# INC-IO1212001.net
KiCad netlist of a schematic drawn in Altium Designer
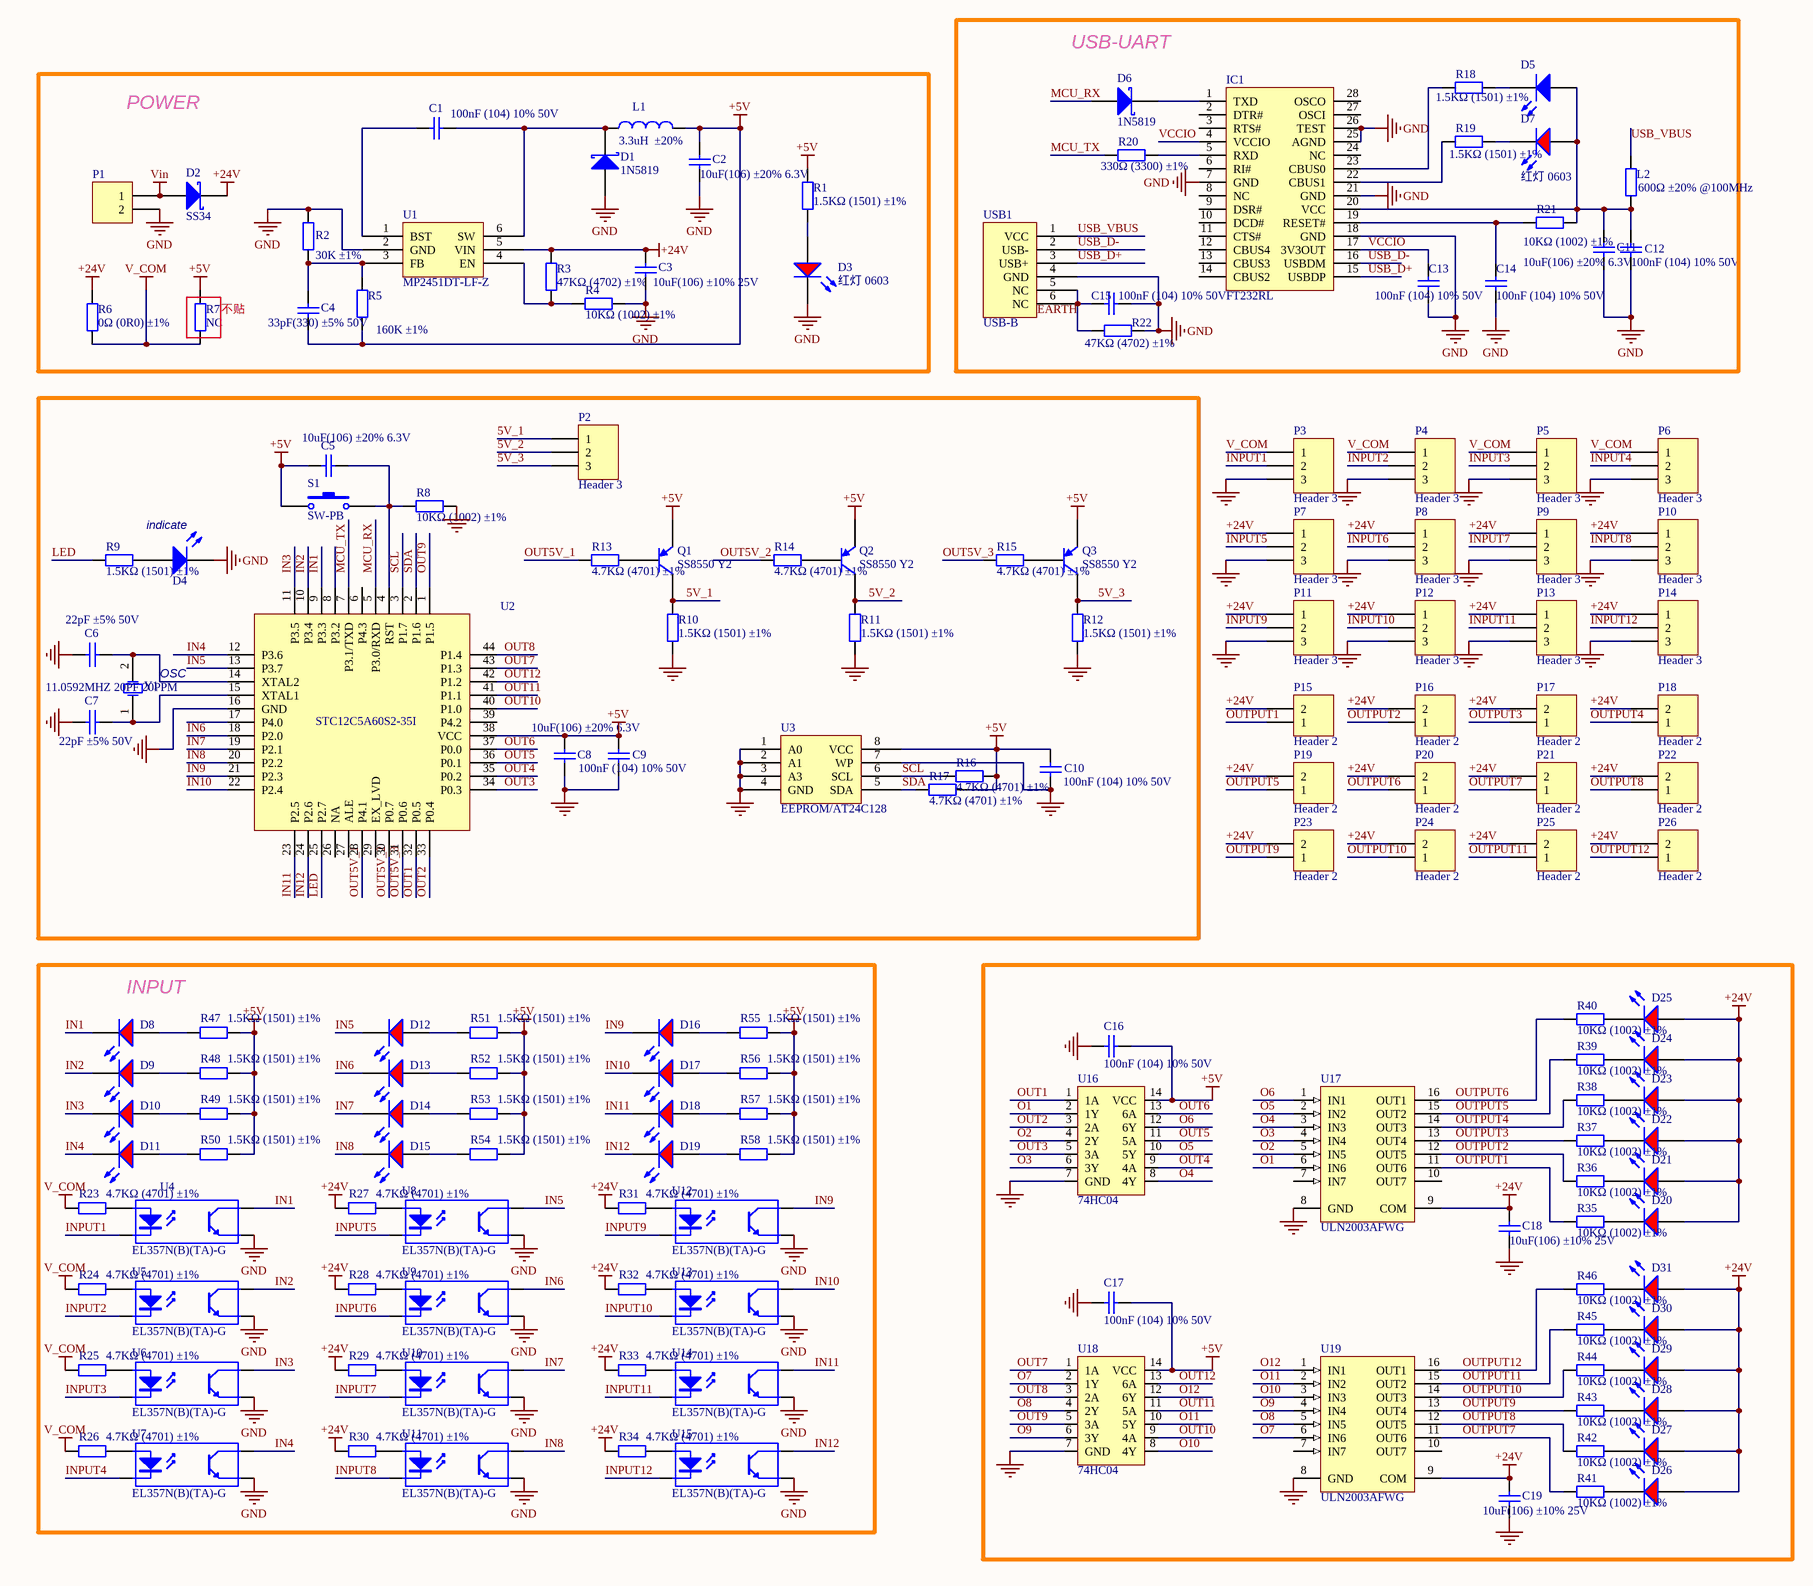
[diagram p0: INC-IO1212001.SchDoc]

(export (version "E")
  (design (tool "Eeschema 10.0.6"))
  (components
    (comp (ref "C1")
      (value "100nF (104) 10% 50V")
      (footprint "0603_C")
      (description "贴片电容")
      (libsource (lib "Miscellaneous Devices LC") (part "0603 10nF (103) 10% 50V"))
    )
    (comp (ref "C2")
      (value "10uF(106) ±20% 6.3V")
      (footprint "0603_C")
      (description "Capacitor")
      (fields (field (name "PUBLISHER") "Altium Limited"))
      (libsource (lib "Miscellaneous Devices") (part "Cap"))
    )
    (comp (ref "C3")
      (value "10uF(106) ±10% 25V")
      (footprint "1206_C")
      (description "Capacitor")
      (fields (field (name "PUBLISHER") "Altium Limited"))
      (libsource (lib "Miscellaneous Devices") (part "Cap"))
    )
    (comp (ref "C4")
      (value "33pF(330) ±5% 50V")
      (footprint "0603_C")
      (description "贴片电容")
      (libsource (lib "Miscellaneous Devices LC") (part "0603 10nF (103) 10% 50V"))
    )
    (comp (ref "C5")
      (value "10uF(106) ±20% 6.3V")
      (footprint "0603_C")
      (description "贴片电容")
      (libsource (lib "Miscellaneous Devices LC") (part "0603 10uF (106) 10% 10V"))
    )
    (comp (ref "C6")
      (value "22pF ±5% 50V")
      (footprint "0603_C")
      (description "Capacitor")
      (libsource (lib "*") (part "CAP"))
    )
    (comp (ref "C7")
      (value "22pF ±5% 50V")
      (footprint "0603_C")
      (description "Capacitor")
      (libsource (lib "*") (part "CAP"))
    )
    (comp (ref "C8")
      (value "10uF(106) ±20% 6.3V")
      (footprint "0603_C")
      (description "Capacitor")
      (fields (field (name "PUBLISHER") "Altium Limited"))
      (libsource (lib "Miscellaneous Devices") (part "Cap"))
    )
    (comp (ref "C9")
      (value "100nF (104) 10% 50V")
      (footprint "0603_C")
      (description "Capacitor")
      (fields (field (name "PUBLISHER") "Altium Limited"))
      (libsource (lib "Miscellaneous Devices") (part "Cap"))
    )
    (comp (ref "C10")
      (value "100nF (104) 10% 50V")
      (footprint "0603_C")
      (description "Capacitor")
      (fields (field (name "PUBLISHER") "Altium Limited"))
      (libsource (lib "Miscellaneous Devices") (part "Cap"))
    )
    (comp (ref "C11")
      (value "10uF(106) ±20% 6.3V")
      (footprint "0603_C")
      (description "Capacitor")
      (fields (field (name "PUBLISHER") "Altium Limited"))
      (libsource (lib "Miscellaneous Devices") (part "Cap"))
    )
    (comp (ref "C12")
      (value "100nF (104) 10% 50V")
      (footprint "0603_C")
      (description "Capacitor")
      (fields (field (name "PUBLISHER") "Altium Limited"))
      (libsource (lib "Miscellaneous Devices") (part "Cap"))
    )
    (comp (ref "C13")
      (value "100nF (104) 10% 50V")
      (footprint "0603_C")
      (description "Capacitor")
      (fields (field (name "PUBLISHER") "Altium Limited"))
      (libsource (lib "Miscellaneous Devices") (part "Cap"))
    )
    (comp (ref "C14")
      (value "100nF (104) 10% 50V")
      (footprint "0603_C")
      (description "Capacitor")
      (fields (field (name "PUBLISHER") "Altium Limited"))
      (libsource (lib "Miscellaneous Devices") (part "Cap"))
    )
    (comp (ref "C15")
      (value "100nF (104) 10% 50V")
      (footprint "0603_C")
      (description "Capacitor")
      (fields (field (name "PUBLISHER") "Altium Limited"))
      (libsource (lib "Miscellaneous Devices") (part "Cap"))
    )
    (comp (ref "C16")
      (value "100nF (104) 10% 50V")
      (footprint "0603_C")
      (description "Capacitor")
      (fields (field (name "PUBLISHER") "Altium Limited"))
      (libsource (lib "Miscellaneous Devices") (part "Cap"))
    )
    (comp (ref "C17")
      (value "100nF (104) 10% 50V")
      (footprint "0603_C")
      (description "Capacitor")
      (fields (field (name "PUBLISHER") "Altium Limited"))
      (libsource (lib "Miscellaneous Devices") (part "Cap"))
    )
    (comp (ref "C18")
      (value "10uF(106) ±10% 25V")
      (footprint "1206_C")
      (description "Capacitor")
      (fields (field (name "PUBLISHER") "Altium Limited"))
      (libsource (lib "Miscellaneous Devices") (part "Cap"))
    )
    (comp (ref "C19")
      (value "10uF(106) ±10% 25V")
      (footprint "1206_C")
      (description "Capacitor")
      (fields (field (name "PUBLISHER") "Altium Limited"))
      (libsource (lib "Miscellaneous Devices") (part "Cap"))
    )
    (comp (ref "D1")
      (value "1N5819")
      (footprint "SOD-123")
      (description "Schottky Diode")
      (fields (field (name "PUBLISHER") "Altium Limited"))
      (libsource (lib "Miscellaneous Devices") (part "D Schottky"))
    )
    (comp (ref "D2")
      (value "SS34")
      (footprint "SMA(DO-214AC)_S1")
      (description "Schottky Diode")
      (fields (field (name "PUBLISHER") "Altium Limited"))
      (libsource (lib "Miscellaneous Devices") (part "D Schottky"))
    )
    (comp (ref "D3")
      (value "红灯 0603")
      (footprint "0603_LED_S1")
      (description "发光二极管")
      (libsource (lib "Miscellaneous Devices LC") (part "0603 红灯"))
    )
    (comp (ref "D4")
      (value "蓝灯 0603")
      (footprint "0603_LED_S1")
      (description "发光二极管")
      (libsource (lib "Miscellaneous Devices LC") (part "0603 蓝灯"))
    )
    (comp (ref "D5")
      (value "蓝灯 0603")
      (footprint "0603_LED_S1")
      (description "发光二极管")
      (libsource (lib "Miscellaneous Devices LC") (part "0603 蓝灯"))
    )
    (comp (ref "D6")
      (value "1N5819")
      (footprint "SOD-123")
      (description "Schottky Diode")
      (fields (field (name "PUBLISHER") "Altium Limited"))
      (libsource (lib "Miscellaneous Devices") (part "D Schottky"))
    )
    (comp (ref "D7")
      (value "红灯 0603")
      (footprint "0603_LED_S1")
      (description "发光二极管")
      (libsource (lib "Miscellaneous Devices LC") (part "0603 红灯"))
    )
    (comp (ref "D8")
      (value "红灯 0603")
      (footprint "0603_LED_S1")
      (description "发光二极管")
      (libsource (lib "Miscellaneous Devices LC") (part "0603 红灯"))
    )
    (comp (ref "D9")
      (value "红灯 0603")
      (footprint "0603_LED_S1")
      (description "发光二极管")
      (libsource (lib "Miscellaneous Devices LC") (part "0603 红灯"))
    )
    (comp (ref "D10")
      (value "红灯 0603")
      (footprint "0603_LED_S1")
      (description "发光二极管")
      (libsource (lib "Miscellaneous Devices LC") (part "0603 红灯"))
    )
    (comp (ref "D11")
      (value "红灯 0603")
      (footprint "0603_LED_S1")
      (description "发光二极管")
      (libsource (lib "Miscellaneous Devices LC") (part "0603 红灯"))
    )
    (comp (ref "D12")
      (value "红灯 0603")
      (footprint "0603_LED_S1")
      (description "发光二极管")
      (libsource (lib "Miscellaneous Devices LC") (part "0603 红灯"))
    )
    (comp (ref "D13")
      (value "红灯 0603")
      (footprint "0603_LED_S1")
      (description "发光二极管")
      (libsource (lib "Miscellaneous Devices LC") (part "0603 红灯"))
    )
    (comp (ref "D14")
      (value "红灯 0603")
      (footprint "0603_LED_S1")
      (description "发光二极管")
      (libsource (lib "Miscellaneous Devices LC") (part "0603 红灯"))
    )
    (comp (ref "D15")
      (value "红灯 0603")
      (footprint "0603_LED_S1")
      (description "发光二极管")
      (libsource (lib "Miscellaneous Devices LC") (part "0603 红灯"))
    )
    (comp (ref "D16")
      (value "红灯 0603")
      (footprint "0603_LED_S1")
      (description "发光二极管")
      (libsource (lib "Miscellaneous Devices LC") (part "0603 红灯"))
    )
    (comp (ref "D17")
      (value "红灯 0603")
      (footprint "0603_LED_S1")
      (description "发光二极管")
      (libsource (lib "Miscellaneous Devices LC") (part "0603 红灯"))
    )
    (comp (ref "D18")
      (value "红灯 0603")
      (footprint "0603_LED_S1")
      (description "发光二极管")
      (libsource (lib "Miscellaneous Devices LC") (part "0603 红灯"))
    )
    (comp (ref "D19")
      (value "红灯 0603")
      (footprint "0603_LED_S1")
      (description "发光二极管")
      (libsource (lib "Miscellaneous Devices LC") (part "0603 红灯"))
    )
    (comp (ref "D20")
      (value "红灯 0603")
      (footprint "0603_LED_S1")
      (description "发光二极管")
      (libsource (lib "Miscellaneous Devices LC") (part "0603 红灯"))
    )
    (comp (ref "D21")
      (value "红灯 0603")
      (footprint "0603_LED_S1")
      (description "发光二极管")
      (libsource (lib "Miscellaneous Devices LC") (part "0603 红灯"))
    )
    (comp (ref "D22")
      (value "红灯 0603")
      (footprint "0603_LED_S1")
      (description "发光二极管")
      (libsource (lib "Miscellaneous Devices LC") (part "0603 红灯"))
    )
    (comp (ref "D23")
      (value "红灯 0603")
      (footprint "0603_LED_S1")
      (description "发光二极管")
      (libsource (lib "Miscellaneous Devices LC") (part "0603 红灯"))
    )
    (comp (ref "D24")
      (value "红灯 0603")
      (footprint "0603_LED_S1")
      (description "发光二极管")
      (libsource (lib "Miscellaneous Devices LC") (part "0603 红灯"))
    )
    (comp (ref "D25")
      (value "红灯 0603")
      (footprint "0603_LED_S1")
      (description "发光二极管")
      (libsource (lib "Miscellaneous Devices LC") (part "0603 红灯"))
    )
    (comp (ref "D26")
      (value "红灯 0603")
      (footprint "0603_LED_S1")
      (description "发光二极管")
      (libsource (lib "Miscellaneous Devices LC") (part "0603 红灯"))
    )
    (comp (ref "D27")
      (value "红灯 0603")
      (footprint "0603_LED_S1")
      (description "发光二极管")
      (libsource (lib "Miscellaneous Devices LC") (part "0603 红灯"))
    )
    (comp (ref "D28")
      (value "红灯 0603")
      (footprint "0603_LED_S1")
      (description "发光二极管")
      (libsource (lib "Miscellaneous Devices LC") (part "0603 红灯"))
    )
    (comp (ref "D29")
      (value "红灯 0603")
      (footprint "0603_LED_S1")
      (description "发光二极管")
      (libsource (lib "Miscellaneous Devices LC") (part "0603 红灯"))
    )
    (comp (ref "D30")
      (value "红灯 0603")
      (footprint "0603_LED_S1")
      (description "发光二极管")
      (libsource (lib "Miscellaneous Devices LC") (part "0603 红灯"))
    )
    (comp (ref "D31")
      (value "红灯 0603")
      (footprint "0603_LED_S1")
      (description "发光二极管")
      (libsource (lib "Miscellaneous Devices LC") (part "0603 红灯"))
    )
    (comp (ref "IC1")
      (value "FT232RL")
      (footprint "SSOP-28_208mil")
      (libsource (lib "GB-SCH") (part "FT232RL"))
    )
    (comp (ref "L1")
      (value "3.3uH  ±20%")
      (footprint "L5020")
      (description "Inductor")
      (fields (field (name "PUBLISHER") "Altium Limited"))
      (libsource (lib "Miscellaneous Devices") (part "Inductor"))
    )
    (comp (ref "L2")
      (value "600Ω ±20% @100MHz")
      (footprint "0805_L")
      (description "Resistor")
      (fields (field (name "PUBLISHER") "Altium Limited"))
      (libsource (lib "Miscellaneous Devices") (part "Res2"))
    )
    (comp (ref "P1")
      (value "Header 2")
      (footprint "GX-2P-3.81MM")
      (description "Header, 2-Pin")
      (fields (field (name "PUBLISHER") "Altium Limited"))
      (libsource (lib "") (part "Header 2_1"))
    )
    (comp (ref "P2")
      (value "Header 3")
      (footprint "GX-3P-3.81MM")
      (description "Header, 3-Pin")
      (fields (field (name "PUBLISHER") "Altium Limited"))
      (libsource (lib "Miscellaneous Connectors") (part "Header 3"))
    )
    (comp (ref "P3")
      (value "Header 3")
      (footprint "GX-3P-3.81MM")
      (description "Header, 3-Pin")
      (fields (field (name "PUBLISHER") "Altium Limited"))
      (libsource (lib "Miscellaneous Connectors") (part "Header 3"))
    )
    (comp (ref "P4")
      (value "Header 3")
      (footprint "GX-3P-3.81MM")
      (description "Header, 3-Pin")
      (fields (field (name "PUBLISHER") "Altium Limited"))
      (libsource (lib "Miscellaneous Connectors") (part "Header 3"))
    )
    (comp (ref "P5")
      (value "Header 3")
      (footprint "GX-3P-3.81MM")
      (description "Header, 3-Pin")
      (fields (field (name "PUBLISHER") "Altium Limited"))
      (libsource (lib "Miscellaneous Connectors") (part "Header 3"))
    )
    (comp (ref "P6")
      (value "Header 3")
      (footprint "GX-3P-3.81MM")
      (description "Header, 3-Pin")
      (fields (field (name "PUBLISHER") "Altium Limited"))
      (libsource (lib "Miscellaneous Connectors") (part "Header 3"))
    )
    (comp (ref "P7")
      (value "Header 3")
      (footprint "GX-3P-3.81MM")
      (description "Header, 3-Pin")
      (fields (field (name "PUBLISHER") "Altium Limited"))
      (libsource (lib "Miscellaneous Connectors") (part "Header 3"))
    )
    (comp (ref "P8")
      (value "Header 3")
      (footprint "GX-3P-3.81MM")
      (description "Header, 3-Pin")
      (fields (field (name "PUBLISHER") "Altium Limited"))
      (libsource (lib "Miscellaneous Connectors") (part "Header 3"))
    )
    (comp (ref "P9")
      (value "Header 3")
      (footprint "GX-3P-3.81MM")
      (description "Header, 3-Pin")
      (fields (field (name "PUBLISHER") "Altium Limited"))
      (libsource (lib "Miscellaneous Connectors") (part "Header 3"))
    )
    (comp (ref "P10")
      (value "Header 3")
      (footprint "GX-3P-3.81MM")
      (description "Header, 3-Pin")
      (fields (field (name "PUBLISHER") "Altium Limited"))
      (libsource (lib "Miscellaneous Connectors") (part "Header 3"))
    )
    (comp (ref "P11")
      (value "Header 3")
      (footprint "GX-3P-3.81MM")
      (description "Header, 3-Pin")
      (fields (field (name "PUBLISHER") "Altium Limited"))
      (libsource (lib "Miscellaneous Connectors") (part "Header 3"))
    )
    (comp (ref "P12")
      (value "Header 3")
      (footprint "GX-3P-3.81MM")
      (description "Header, 3-Pin")
      (fields (field (name "PUBLISHER") "Altium Limited"))
      (libsource (lib "Miscellaneous Connectors") (part "Header 3"))
    )
    (comp (ref "P13")
      (value "Header 3")
      (footprint "GX-3P-3.81MM")
      (description "Header, 3-Pin")
      (fields (field (name "PUBLISHER") "Altium Limited"))
      (libsource (lib "Miscellaneous Connectors") (part "Header 3"))
    )
    (comp (ref "P14")
      (value "Header 3")
      (footprint "GX-3P-3.81MM")
      (description "Header, 3-Pin")
      (fields (field (name "PUBLISHER") "Altium Limited"))
      (libsource (lib "Miscellaneous Connectors") (part "Header 3"))
    )
    (comp (ref "P15")
      (value "Header 2")
      (footprint "GX-2P-3.81MM")
      (description "Header, 2-Pin")
      (fields (field (name "PUBLISHER") "Altium Limited"))
      (libsource (lib "Miscellaneous Connectors") (part "Header 2"))
    )
    (comp (ref "P16")
      (value "Header 2")
      (footprint "GX-2P-3.81MM")
      (description "Header, 2-Pin")
      (fields (field (name "PUBLISHER") "Altium Limited"))
      (libsource (lib "Miscellaneous Connectors") (part "Header 2"))
    )
    (comp (ref "P17")
      (value "Header 2")
      (footprint "GX-2P-3.81MM")
      (description "Header, 2-Pin")
      (fields (field (name "PUBLISHER") "Altium Limited"))
      (libsource (lib "Miscellaneous Connectors") (part "Header 2"))
    )
    (comp (ref "P18")
      (value "Header 2")
      (footprint "GX-2P-3.81MM")
      (description "Header, 2-Pin")
      (fields (field (name "PUBLISHER") "Altium Limited"))
      (libsource (lib "Miscellaneous Connectors") (part "Header 2"))
    )
    (comp (ref "P19")
      (value "Header 2")
      (footprint "GX-2P-3.81MM")
      (description "Header, 2-Pin")
      (fields (field (name "PUBLISHER") "Altium Limited"))
      (libsource (lib "Miscellaneous Connectors") (part "Header 2"))
    )
    (comp (ref "P20")
      (value "Header 2")
      (footprint "GX-2P-3.81MM")
      (description "Header, 2-Pin")
      (fields (field (name "PUBLISHER") "Altium Limited"))
      (libsource (lib "Miscellaneous Connectors") (part "Header 2"))
    )
    (comp (ref "P21")
      (value "Header 2")
      (footprint "GX-2P-3.81MM")
      (description "Header, 2-Pin")
      (fields (field (name "PUBLISHER") "Altium Limited"))
      (libsource (lib "Miscellaneous Connectors") (part "Header 2"))
    )
    (comp (ref "P22")
      (value "Header 2")
      (footprint "GX-2P-3.81MM")
      (description "Header, 2-Pin")
      (fields (field (name "PUBLISHER") "Altium Limited"))
      (libsource (lib "Miscellaneous Connectors") (part "Header 2"))
    )
    (comp (ref "P23")
      (value "Header 2")
      (footprint "GX-2P-3.81MM")
      (description "Header, 2-Pin")
      (fields (field (name "PUBLISHER") "Altium Limited"))
      (libsource (lib "Miscellaneous Connectors") (part "Header 2"))
    )
    (comp (ref "P24")
      (value "Header 2")
      (footprint "GX-2P-3.81MM")
      (description "Header, 2-Pin")
      (fields (field (name "PUBLISHER") "Altium Limited"))
      (libsource (lib "Miscellaneous Connectors") (part "Header 2"))
    )
    (comp (ref "P25")
      (value "Header 2")
      (footprint "GX-2P-3.81MM")
      (description "Header, 2-Pin")
      (fields (field (name "PUBLISHER") "Altium Limited"))
      (libsource (lib "Miscellaneous Connectors") (part "Header 2"))
    )
    (comp (ref "P26")
      (value "Header 2")
      (footprint "GX-2P-3.81MM")
      (description "Header, 2-Pin")
      (fields (field (name "PUBLISHER") "Altium Limited"))
      (libsource (lib "Miscellaneous Connectors") (part "Header 2"))
    )
    (comp (ref "Q1")
      (value "SS8550 Y2")
      (footprint "SOT-23(SOT-23-3)")
      (description "三极管")
      (libsource (lib "Miscellaneous Devices LC") (part "SOT-23 SS8550 Y2"))
    )
    (comp (ref "Q2")
      (value "SS8550 Y2")
      (footprint "SOT-23(SOT-23-3)")
      (description "三极管")
      (libsource (lib "Miscellaneous Devices LC") (part "SOT-23 SS8550 Y2"))
    )
    (comp (ref "Q3")
      (value "SS8550 Y2")
      (footprint "SOT-23(SOT-23-3)")
      (description "三极管")
      (libsource (lib "Miscellaneous Devices LC") (part "SOT-23 SS8550 Y2"))
    )
    (comp (ref "R1")
      (value "1.5KΩ (1501) ±1%")
      (footprint "0603_R")
      (description "贴片电阻")
      (libsource (lib "") (part "0603 1KΩ (1001) 1%_1"))
    )
    (comp (ref "R2")
      (value "30K ±1%")
      (footprint "0603_R")
      (description "贴片电阻")
      (libsource (lib "Miscellaneous Devices LC") (part "0603 18KΩ (1802) 1%"))
    )
    (comp (ref "R3")
      (value "47KΩ (4702) ±1%")
      (footprint "0603_R")
      (description "贴片电阻")
      (libsource (lib "") (part "0603 100KΩ (1003) 1%_1"))
    )
    (comp (ref "R4")
      (value "10KΩ (1002) ±1%")
      (footprint "0603_R")
      (description "贴片电阻")
      (libsource (lib "Miscellaneous Devices LC") (part "0603 100KΩ (1003) 1%"))
    )
    (comp (ref "R5")
      (value "160K ±1%")
      (footprint "0603_R")
      (description "贴片电阻")
      (libsource (lib "Miscellaneous Devices LC") (part "0603 18KΩ (1802) 1%"))
    )
    (comp (ref "R6")
      (value "0Ω (0R0) ±1%")
      (footprint "0603_R")
      (description "贴片电阻")
      (libsource (lib "") (part "0603 18KΩ (1802) 1%_2"))
    )
    (comp (ref "R7")
      (value "NC")
      (footprint "0603_R")
      (description "贴片电阻")
      (libsource (lib "") (part "0603 18KΩ (1802) 1%_2"))
    )
    (comp (ref "R8")
      (value "10KΩ (1002) ±1%")
      (footprint "0603_R")
      (description "贴片电阻")
      (libsource (lib "Miscellaneous Devices LC") (part "0603 1KΩ (1001) 1%"))
    )
    (comp (ref "R9")
      (value "1.5KΩ (1501) ±1%")
      (footprint "0603_R")
      (description "Resistor")
      (fields (field (name "PUBLISHER") "Altium Limited"))
      (libsource (lib "") (part "Res2_1"))
    )
    (comp (ref "R10")
      (value "1.5KΩ (1501) ±1%")
      (footprint "0603_R")
      (description "贴片电阻")
      (libsource (lib "") (part "0603 1KΩ (1001) 1%_2"))
    )
    (comp (ref "R11")
      (value "1.5KΩ (1501) ±1%")
      (footprint "0603_R")
      (description "贴片电阻")
      (libsource (lib "") (part "0603 1KΩ (1001) 1%_2"))
    )
    (comp (ref "R12")
      (value "1.5KΩ (1501) ±1%")
      (footprint "0603_R")
      (description "贴片电阻")
      (libsource (lib "") (part "0603 1KΩ (1001) 1%_2"))
    )
    (comp (ref "R13")
      (value "4.7KΩ (4701) ±1%")
      (footprint "0603_R")
      (description "贴片电阻")
      (libsource (lib "Miscellaneous Devices LC") (part "0603 1KΩ (1001) 1%"))
    )
    (comp (ref "R14")
      (value "4.7KΩ (4701) ±1%")
      (footprint "0603_R")
      (description "贴片电阻")
      (libsource (lib "Miscellaneous Devices LC") (part "0603 1KΩ (1001) 1%"))
    )
    (comp (ref "R15")
      (value "4.7KΩ (4701) ±1%")
      (footprint "0603_R")
      (description "贴片电阻")
      (libsource (lib "Miscellaneous Devices LC") (part "0603 1KΩ (1001) 1%"))
    )
    (comp (ref "R16")
      (value "4.7KΩ (4701) ±1%")
      (footprint "0603_R")
      (description "贴片电阻")
      (libsource (lib "Miscellaneous Devices LC") (part "0603 1KΩ (1001) 1%"))
    )
    (comp (ref "R17")
      (value "4.7KΩ (4701) ±1%")
      (footprint "0603_R")
      (description "贴片电阻")
      (libsource (lib "Miscellaneous Devices LC") (part "0603 1KΩ (1001) 1%"))
    )
    (comp (ref "R18")
      (value "1.5KΩ (1501) ±1%")
      (footprint "0603_R")
      (description "Resistor")
      (fields (field (name "PUBLISHER") "Altium Limited"))
      (libsource (lib "Miscellaneous Devices") (part "Res2"))
    )
    (comp (ref "R19")
      (value "1.5KΩ (1501) ±1%")
      (footprint "0603_R")
      (description "Resistor")
      (fields (field (name "PUBLISHER") "Altium Limited"))
      (libsource (lib "Miscellaneous Devices") (part "Res2"))
    )
    (comp (ref "R20")
      (value "330Ω (3300) ±1%")
      (footprint "0603_R")
      (description "Resistor")
      (fields (field (name "PUBLISHER") "Altium Limited"))
      (libsource (lib "") (part "Res2_1"))
    )
    (comp (ref "R21")
      (value "10KΩ (1002) ±1%")
      (footprint "0603_R")
      (description "Resistor")
      (fields (field (name "PUBLISHER") "Altium Limited"))
      (libsource (lib "") (part "Res2_3"))
    )
    (comp (ref "R22")
      (value "47KΩ (4702) ±1%")
      (footprint "0603_R")
      (description "Resistor")
      (fields (field (name "PUBLISHER") "Altium Limited"))
      (libsource (lib "") (part "Res2_2"))
    )
    (comp (ref "R23")
      (value "4.7KΩ (4701) ±1%")
      (footprint "1210_R")
      (description "贴片电阻")
      (libsource (lib "") (part "0603 18KΩ (1802) 1%_1"))
    )
    (comp (ref "R24")
      (value "4.7KΩ (4701) ±1%")
      (footprint "1210_R")
      (description "贴片电阻")
      (libsource (lib "") (part "0603 18KΩ (1802) 1%_1"))
    )
    (comp (ref "R25")
      (value "4.7KΩ (4701) ±1%")
      (footprint "1210_R")
      (description "贴片电阻")
      (libsource (lib "") (part "0603 18KΩ (1802) 1%_1"))
    )
    (comp (ref "R26")
      (value "4.7KΩ (4701) ±1%")
      (footprint "1210_R")
      (description "贴片电阻")
      (libsource (lib "") (part "0603 18KΩ (1802) 1%_1"))
    )
    (comp (ref "R27")
      (value "4.7KΩ (4701) ±1%")
      (footprint "1210_R")
      (description "贴片电阻")
      (libsource (lib "") (part "0603 18KΩ (1802) 1%_1"))
    )
    (comp (ref "R28")
      (value "4.7KΩ (4701) ±1%")
      (footprint "1210_R")
      (description "贴片电阻")
      (libsource (lib "") (part "0603 18KΩ (1802) 1%_1"))
    )
    (comp (ref "R29")
      (value "4.7KΩ (4701) ±1%")
      (footprint "1210_R")
      (description "贴片电阻")
      (libsource (lib "") (part "0603 18KΩ (1802) 1%_1"))
    )
    (comp (ref "R30")
      (value "4.7KΩ (4701) ±1%")
      (footprint "1210_R")
      (description "贴片电阻")
      (libsource (lib "") (part "0603 18KΩ (1802) 1%_1"))
    )
    (comp (ref "R31")
      (value "4.7KΩ (4701) ±1%")
      (footprint "1210_R")
      (description "贴片电阻")
      (libsource (lib "") (part "0603 18KΩ (1802) 1%_1"))
    )
    (comp (ref "R32")
      (value "4.7KΩ (4701) ±1%")
      (footprint "1210_R")
      (description "贴片电阻")
      (libsource (lib "") (part "0603 18KΩ (1802) 1%_1"))
    )
    (comp (ref "R33")
      (value "4.7KΩ (4701) ±1%")
      (footprint "1210_R")
      (description "贴片电阻")
      (libsource (lib "") (part "0603 18KΩ (1802) 1%_1"))
    )
    (comp (ref "R34")
      (value "4.7KΩ (4701) ±1%")
      (footprint "1210_R")
      (description "贴片电阻")
      (libsource (lib "") (part "0603 18KΩ (1802) 1%_1"))
    )
    (comp (ref "R35")
      (value "10KΩ (1002) ±1%")
      (footprint "0603_R")
      (description "贴片电阻")
      (libsource (lib "Miscellaneous Devices LC") (part "0603 1KΩ (1001) 1%"))
    )
    (comp (ref "R36")
      (value "10KΩ (1002) ±1%")
      (footprint "0603_R")
      (description "贴片电阻")
      (libsource (lib "Miscellaneous Devices LC") (part "0603 1KΩ (1001) 1%"))
    )
    (comp (ref "R37")
      (value "10KΩ (1002) ±1%")
      (footprint "0603_R")
      (description "贴片电阻")
      (libsource (lib "Miscellaneous Devices LC") (part "0603 1KΩ (1001) 1%"))
    )
    (comp (ref "R38")
      (value "10KΩ (1002) ±1%")
      (footprint "0603_R")
      (description "贴片电阻")
      (libsource (lib "Miscellaneous Devices LC") (part "0603 1KΩ (1001) 1%"))
    )
    (comp (ref "R39")
      (value "10KΩ (1002) ±1%")
      (footprint "0603_R")
      (description "贴片电阻")
      (libsource (lib "Miscellaneous Devices LC") (part "0603 1KΩ (1001) 1%"))
    )
    (comp (ref "R40")
      (value "10KΩ (1002) ±1%")
      (footprint "0603_R")
      (description "贴片电阻")
      (libsource (lib "Miscellaneous Devices LC") (part "0603 1KΩ (1001) 1%"))
    )
    (comp (ref "R41")
      (value "10KΩ (1002) ±1%")
      (footprint "0603_R")
      (description "贴片电阻")
      (libsource (lib "Miscellaneous Devices LC") (part "0603 1KΩ (1001) 1%"))
    )
    (comp (ref "R42")
      (value "10KΩ (1002) ±1%")
      (footprint "0603_R")
      (description "贴片电阻")
      (libsource (lib "Miscellaneous Devices LC") (part "0603 1KΩ (1001) 1%"))
    )
    (comp (ref "R43")
      (value "10KΩ (1002) ±1%")
      (footprint "0603_R")
      (description "贴片电阻")
      (libsource (lib "Miscellaneous Devices LC") (part "0603 1KΩ (1001) 1%"))
    )
    (comp (ref "R44")
      (value "10KΩ (1002) ±1%")
      (footprint "0603_R")
      (description "贴片电阻")
      (libsource (lib "Miscellaneous Devices LC") (part "0603 1KΩ (1001) 1%"))
    )
    (comp (ref "R45")
      (value "10KΩ (1002) ±1%")
      (footprint "0603_R")
      (description "贴片电阻")
      (libsource (lib "Miscellaneous Devices LC") (part "0603 1KΩ (1001) 1%"))
    )
    (comp (ref "R46")
      (value "10KΩ (1002) ±1%")
      (footprint "0603_R")
      (description "贴片电阻")
      (libsource (lib "Miscellaneous Devices LC") (part "0603 1KΩ (1001) 1%"))
    )
    (comp (ref "R47")
      (value "1.5KΩ (1501) ±1%")
      (footprint "0603_R")
      (description "贴片电阻")
      (libsource (lib "") (part "0603 18KΩ (1802) 1%_1"))
    )
    (comp (ref "R48")
      (value "1.5KΩ (1501) ±1%")
      (footprint "0603_R")
      (description "贴片电阻")
      (libsource (lib "") (part "0603 18KΩ (1802) 1%_1"))
    )
    (comp (ref "R49")
      (value "1.5KΩ (1501) ±1%")
      (footprint "0603_R")
      (description "贴片电阻")
      (libsource (lib "") (part "0603 18KΩ (1802) 1%_1"))
    )
    (comp (ref "R50")
      (value "1.5KΩ (1501) ±1%")
      (footprint "0603_R")
      (description "贴片电阻")
      (libsource (lib "") (part "0603 18KΩ (1802) 1%_1"))
    )
    (comp (ref "R51")
      (value "1.5KΩ (1501) ±1%")
      (footprint "0603_R")
      (description "贴片电阻")
      (libsource (lib "") (part "0603 18KΩ (1802) 1%_1"))
    )
    (comp (ref "R52")
      (value "1.5KΩ (1501) ±1%")
      (footprint "0603_R")
      (description "贴片电阻")
      (libsource (lib "") (part "0603 18KΩ (1802) 1%_1"))
    )
    (comp (ref "R53")
      (value "1.5KΩ (1501) ±1%")
      (footprint "0603_R")
      (description "贴片电阻")
      (libsource (lib "") (part "0603 18KΩ (1802) 1%_1"))
    )
    (comp (ref "R54")
      (value "1.5KΩ (1501) ±1%")
      (footprint "0603_R")
      (description "贴片电阻")
      (libsource (lib "") (part "0603 18KΩ (1802) 1%_1"))
    )
    (comp (ref "R55")
      (value "1.5KΩ (1501) ±1%")
      (footprint "0603_R")
      (description "贴片电阻")
      (libsource (lib "") (part "0603 18KΩ (1802) 1%_1"))
    )
    (comp (ref "R56")
      (value "1.5KΩ (1501) ±1%")
      (footprint "0603_R")
      (description "贴片电阻")
      (libsource (lib "") (part "0603 18KΩ (1802) 1%_1"))
    )
    (comp (ref "R57")
      (value "1.5KΩ (1501) ±1%")
      (footprint "0603_R")
      (description "贴片电阻")
      (libsource (lib "") (part "0603 18KΩ (1802) 1%_1"))
    )
    (comp (ref "R58")
      (value "1.5KΩ (1501) ±1%")
      (footprint "0603_R")
      (description "贴片电阻")
      (libsource (lib "") (part "0603 18KΩ (1802) 1%_1"))
    )
    (comp (ref "S1")
      (value "SW-PB")
      (footprint "SW-3*6*2.5")
      (description "Switch")
      (fields (field (name "PUBLISHER") "Altium Limited"))
      (libsource (lib "Miscellaneous Devices") (part "SW-PB"))
    )
    (comp (ref "U1")
      (value "MP2451DT-LF-Z")
      (footprint "SOT-23-6")
      (description "DC-DC芯片")
      (libsource (lib "Miscellaneous Devices LC") (part "MP2451DT-LF-Z"))
    )
    (comp (ref "U2")
      (value "STC12C5A60S2-35I")
      (footprint "LQFP-44_10x10x08P")
      (description "MCU")
      (libsource (lib "Miscellaneous Devices LC") (part "STC12C5A60S2-35I"))
    )
    (comp (ref "U3")
      (value "EEPROM/AT24C128")
      (footprint "SOIC-8_150mil")
      (description "EEPROM")
      (libsource (lib "Miscellaneous Devices LC") (part "EEPROM/AT24C256C-SSHL-T"))
    )
    (comp (ref "U4")
      (value "EL357N(B)(TA)-G")
      (footprint "SOP-4_P2.54")
      (description "贴片光耦")
      (libsource (lib "Miscellaneous Devices LC") (part "EL357N(B)(TA)-G"))
    )
    (comp (ref "U5")
      (value "EL357N(B)(TA)-G")
      (footprint "SOP-4_P2.54")
      (description "贴片光耦")
      (libsource (lib "Miscellaneous Devices LC") (part "EL357N(B)(TA)-G"))
    )
    (comp (ref "U6")
      (value "EL357N(B)(TA)-G")
      (footprint "SOP-4_P2.54")
      (description "贴片光耦")
      (libsource (lib "Miscellaneous Devices LC") (part "EL357N(B)(TA)-G"))
    )
    (comp (ref "U7")
      (value "EL357N(B)(TA)-G")
      (footprint "SOP-4_P2.54")
      (description "贴片光耦")
      (libsource (lib "Miscellaneous Devices LC") (part "EL357N(B)(TA)-G"))
    )
    (comp (ref "U8")
      (value "EL357N(B)(TA)-G")
      (footprint "SOP-4_P2.54")
      (description "贴片光耦")
      (libsource (lib "Miscellaneous Devices LC") (part "EL357N(B)(TA)-G"))
    )
    (comp (ref "U9")
      (value "EL357N(B)(TA)-G")
      (footprint "SOP-4_P2.54")
      (description "贴片光耦")
      (libsource (lib "Miscellaneous Devices LC") (part "EL357N(B)(TA)-G"))
    )
    (comp (ref "U10")
      (value "EL357N(B)(TA)-G")
      (footprint "SOP-4_P2.54")
      (description "贴片光耦")
      (libsource (lib "Miscellaneous Devices LC") (part "EL357N(B)(TA)-G"))
    )
    (comp (ref "U11")
      (value "EL357N(B)(TA)-G")
      (footprint "SOP-4_P2.54")
      (description "贴片光耦")
      (libsource (lib "Miscellaneous Devices LC") (part "EL357N(B)(TA)-G"))
    )
    (comp (ref "U12")
      (value "EL357N(B)(TA)-G")
      (footprint "SOP-4_P2.54")
      (description "贴片光耦")
      (libsource (lib "Miscellaneous Devices LC") (part "EL357N(B)(TA)-G"))
    )
    (comp (ref "U13")
      (value "EL357N(B)(TA)-G")
      (footprint "SOP-4_P2.54")
      (description "贴片光耦")
      (libsource (lib "Miscellaneous Devices LC") (part "EL357N(B)(TA)-G"))
    )
    (comp (ref "U14")
      (value "EL357N(B)(TA)-G")
      (footprint "SOP-4_P2.54")
      (description "贴片光耦")
      (libsource (lib "Miscellaneous Devices LC") (part "EL357N(B)(TA)-G"))
    )
    (comp (ref "U15")
      (value "EL357N(B)(TA)-G")
      (footprint "SOP-4_P2.54")
      (description "贴片光耦")
      (libsource (lib "Miscellaneous Devices LC") (part "EL357N(B)(TA)-G"))
    )
    (comp (ref "U16")
      (value "74HC04")
      (footprint "SOIC-14_150mil")
      (libsource (lib "XCP-SCH_V1.00") (part "74HC04"))
    )
    (comp (ref "U17")
      (value "ULN2003AFWG")
      (footprint "SOIC-16_150mil")
      (description "大电流驱动")
      (libsource (lib "Miscellaneous Devices LC") (part "ULN2003AFWG"))
    )
    (comp (ref "U18")
      (value "74HC04")
      (footprint "SOIC-14_150mil")
      (libsource (lib "XCP-SCH_V1.00") (part "74HC04"))
    )
    (comp (ref "U19")
      (value "ULN2003AFWG")
      (footprint "SOIC-16_150mil")
      (description "大电流驱动")
      (libsource (lib "Miscellaneous Devices LC") (part "ULN2003AFWG"))
    )
    (comp (ref "USB1") (value "USB-B") (footprint "USB-b") (libsource (lib "GB-SCH") (part "USB-6")))
    (comp (ref "Y1")
      (value "11.0592MHZ 20PF 20PPM")
      (footprint "SMD-5032_2P")
      (description "贴片晶振")
      (libsource (lib "Miscellaneous Devices LC") (part "SMD-5032_2P 11.0592MHZ 20PF 20PPM"))
    )
  )
  (nets
    (net (code "1") (name "+5V") (class "Default")
      (node (ref "C10") (pin "1") (pinfunction "1_1") (pintype "passive"))
      (node (ref "C16") (pin "2") (pinfunction "2_2") (pintype "passive"))
      (node (ref "C17") (pin "2") (pinfunction "2_2") (pintype "passive"))
      (node (ref "C2") (pin "2") (pinfunction "2_2") (pintype "passive"))
      (node (ref "C4") (pin "2") (pinfunction "2_2") (pintype "passive"))
      (node (ref "C5") (pin "2") (pinfunction "2_2") (pintype "passive"))
      (node (ref "C8") (pin "1") (pinfunction "1_1") (pintype "passive"))
      (node (ref "C9") (pin "1") (pinfunction "1_1") (pintype "passive"))
      (node (ref "L1") (pin "2") (pinfunction "2_2") (pintype "passive"))
      (node (ref "Q1") (pin "2") (pinfunction "E_2") (pintype "passive"))
      (node (ref "Q2") (pin "2") (pinfunction "E_2") (pintype "passive"))
      (node (ref "Q3") (pin "2") (pinfunction "E_2") (pintype "passive"))
      (node (ref "R1") (pin "1") (pinfunction "1_1") (pintype "passive"))
      (node (ref "R16") (pin "2") (pinfunction "2_2") (pintype "passive"))
      (node (ref "R17") (pin "2") (pinfunction "2_2") (pintype "passive"))
      (node (ref "R47") (pin "2") (pinfunction "2_2") (pintype "passive"))
      (node (ref "R48") (pin "2") (pinfunction "2_2") (pintype "passive"))
      (node (ref "R49") (pin "2") (pinfunction "2_2") (pintype "passive"))
      (node (ref "R5") (pin "2") (pinfunction "2_2") (pintype "passive"))
      (node (ref "R50") (pin "2") (pinfunction "2_2") (pintype "passive"))
      (node (ref "R51") (pin "2") (pinfunction "2_2") (pintype "passive"))
      (node (ref "R52") (pin "2") (pinfunction "2_2") (pintype "passive"))
      (node (ref "R53") (pin "2") (pinfunction "2_2") (pintype "passive"))
      (node (ref "R54") (pin "2") (pinfunction "2_2") (pintype "passive"))
      (node (ref "R55") (pin "2") (pinfunction "2_2") (pintype "passive"))
      (node (ref "R56") (pin "2") (pinfunction "2_2") (pintype "passive"))
      (node (ref "R57") (pin "2") (pinfunction "2_2") (pintype "passive"))
      (node (ref "R58") (pin "2") (pinfunction "2_2") (pintype "passive"))
      (node (ref "R7") (pin "2") (pinfunction "2_2") (pintype "passive"))
      (node (ref "S1") (pin "1") (pinfunction "1_1") (pintype "passive"))
      (node (ref "U16") (pin "14") (pinfunction "VCC_14") (pintype "passive"))
      (node (ref "U18") (pin "14") (pinfunction "VCC_14") (pintype "passive"))
      (node (ref "U2") (pin "38") (pinfunction "VCC_38") (pintype "power_in"))
      (node (ref "U3") (pin "8") (pinfunction "VCC_8") (pintype "passive"))
    )
    (net (code "2") (name "+24V") (class "Default")
      (node (ref "C18") (pin "2") (pinfunction "2_2") (pintype "passive"))
      (node (ref "C19") (pin "2") (pinfunction "2_2") (pintype "passive"))
      (node (ref "C3") (pin "2") (pinfunction "2_2") (pintype "passive"))
      (node (ref "D2") (pin "2") (pinfunction "K_2") (pintype "passive"))
      (node (ref "D20") (pin "A") (pinfunction "A_A") (pintype "passive"))
      (node (ref "D21") (pin "A") (pinfunction "A_A") (pintype "passive"))
      (node (ref "D22") (pin "A") (pinfunction "A_A") (pintype "passive"))
      (node (ref "D23") (pin "A") (pinfunction "A_A") (pintype "passive"))
      (node (ref "D24") (pin "A") (pinfunction "A_A") (pintype "passive"))
      (node (ref "D25") (pin "A") (pinfunction "A_A") (pintype "passive"))
      (node (ref "D26") (pin "A") (pinfunction "A_A") (pintype "passive"))
      (node (ref "D27") (pin "A") (pinfunction "A_A") (pintype "passive"))
      (node (ref "D28") (pin "A") (pinfunction "A_A") (pintype "passive"))
      (node (ref "D29") (pin "A") (pinfunction "A_A") (pintype "passive"))
      (node (ref "D30") (pin "A") (pinfunction "A_A") (pintype "passive"))
      (node (ref "D31") (pin "A") (pinfunction "A_A") (pintype "passive"))
      (node (ref "P10") (pin "1") (pinfunction "1_1") (pintype "passive"))
      (node (ref "P11") (pin "1") (pinfunction "1_1") (pintype "passive"))
      (node (ref "P12") (pin "1") (pinfunction "1_1") (pintype "passive"))
      (node (ref "P13") (pin "1") (pinfunction "1_1") (pintype "passive"))
      (node (ref "P14") (pin "1") (pinfunction "1_1") (pintype "passive"))
      (node (ref "P15") (pin "2") (pinfunction "2_2") (pintype "passive"))
      (node (ref "P16") (pin "2") (pinfunction "2_2") (pintype "passive"))
      (node (ref "P17") (pin "2") (pinfunction "2_2") (pintype "passive"))
      (node (ref "P18") (pin "2") (pinfunction "2_2") (pintype "passive"))
      (node (ref "P19") (pin "2") (pinfunction "2_2") (pintype "passive"))
      (node (ref "P20") (pin "2") (pinfunction "2_2") (pintype "passive"))
      (node (ref "P21") (pin "2") (pinfunction "2_2") (pintype "passive"))
      (node (ref "P22") (pin "2") (pinfunction "2_2") (pintype "passive"))
      (node (ref "P23") (pin "2") (pinfunction "2_2") (pintype "passive"))
      (node (ref "P24") (pin "2") (pinfunction "2_2") (pintype "passive"))
      (node (ref "P25") (pin "2") (pinfunction "2_2") (pintype "passive"))
      (node (ref "P26") (pin "2") (pinfunction "2_2") (pintype "passive"))
      (node (ref "P7") (pin "1") (pinfunction "1_1") (pintype "passive"))
      (node (ref "P8") (pin "1") (pinfunction "1_1") (pintype "passive"))
      (node (ref "P9") (pin "1") (pinfunction "1_1") (pintype "passive"))
      (node (ref "R27") (pin "1") (pinfunction "1_1") (pintype "passive"))
      (node (ref "R28") (pin "1") (pinfunction "1_1") (pintype "passive"))
      (node (ref "R29") (pin "1") (pinfunction "1_1") (pintype "passive"))
      (node (ref "R3") (pin "1") (pinfunction "1_1") (pintype "passive"))
      (node (ref "R30") (pin "1") (pinfunction "1_1") (pintype "passive"))
      (node (ref "R31") (pin "1") (pinfunction "1_1") (pintype "passive"))
      (node (ref "R32") (pin "1") (pinfunction "1_1") (pintype "passive"))
      (node (ref "R33") (pin "1") (pinfunction "1_1") (pintype "passive"))
      (node (ref "R34") (pin "1") (pinfunction "1_1") (pintype "passive"))
      (node (ref "R6") (pin "2") (pinfunction "2_2") (pintype "passive"))
      (node (ref "U1") (pin "5") (pinfunction "VIN_5") (pintype "passive"))
      (node (ref "U17") (pin "9") (pinfunction "COM_9") (pintype "passive"))
      (node (ref "U19") (pin "9") (pinfunction "COM_9") (pintype "passive"))
    )
    (net (code "3") (name "/5V_1") (class "Default")
      (node (ref "P2") (pin "1") (pinfunction "1_1") (pintype "passive"))
      (node (ref "Q1") (pin "3") (pinfunction "C_3") (pintype "passive"))
      (node (ref "R10") (pin "2") (pinfunction "2_2") (pintype "passive"))
    )
    (net (code "4") (name "/5V_2") (class "Default")
      (node (ref "P2") (pin "2") (pinfunction "2_2") (pintype "passive"))
      (node (ref "Q2") (pin "3") (pinfunction "C_3") (pintype "passive"))
      (node (ref "R11") (pin "2") (pinfunction "2_2") (pintype "passive"))
    )
    (net (code "5") (name "/5V_3") (class "Default")
      (node (ref "P2") (pin "3") (pinfunction "3_3") (pintype "passive"))
      (node (ref "Q3") (pin "3") (pinfunction "C_3") (pintype "passive"))
      (node (ref "R12") (pin "2") (pinfunction "2_2") (pintype "passive"))
    )
    (net (code "7") (name "/IN1") (class "Default")
      (node (ref "D8") (pin "K") (pinfunction "K_K") (pintype "passive"))
      (node (ref "U2") (pin "9") (pinfunction "P3.3_9") (pintype "passive"))
      (node (ref "U4") (pin "4") (pinfunction "C_4") (pintype "passive"))
    )
    (net (code "8") (name "/IN2") (class "Default")
      (node (ref "D9") (pin "K") (pinfunction "K_K") (pintype "passive"))
      (node (ref "U2") (pin "10") (pinfunction "P3.4_10") (pintype "passive"))
      (node (ref "U5") (pin "4") (pinfunction "C_4") (pintype "passive"))
    )
    (net (code "9") (name "/IN3") (class "Default")
      (node (ref "D10") (pin "K") (pinfunction "K_K") (pintype "passive"))
      (node (ref "U2") (pin "11") (pinfunction "P3.5_11") (pintype "passive"))
      (node (ref "U6") (pin "4") (pinfunction "C_4") (pintype "passive"))
    )
    (net (code "10") (name "/IN4") (class "Default")
      (node (ref "D11") (pin "K") (pinfunction "K_K") (pintype "passive"))
      (node (ref "U2") (pin "12") (pinfunction "P3.6_12") (pintype "passive"))
      (node (ref "U7") (pin "4") (pinfunction "C_4") (pintype "passive"))
    )
    (net (code "11") (name "/IN5") (class "Default")
      (node (ref "D12") (pin "K") (pinfunction "K_K") (pintype "passive"))
      (node (ref "U2") (pin "13") (pinfunction "P3.7_13") (pintype "passive"))
      (node (ref "U8") (pin "4") (pinfunction "C_4") (pintype "passive"))
    )
    (net (code "12") (name "/IN6") (class "Default")
      (node (ref "D13") (pin "K") (pinfunction "K_K") (pintype "passive"))
      (node (ref "U2") (pin "18") (pinfunction "P2.0_18") (pintype "passive"))
      (node (ref "U9") (pin "4") (pinfunction "C_4") (pintype "passive"))
    )
    (net (code "13") (name "/IN7") (class "Default")
      (node (ref "D14") (pin "K") (pinfunction "K_K") (pintype "passive"))
      (node (ref "U10") (pin "4") (pinfunction "C_4") (pintype "passive"))
      (node (ref "U2") (pin "19") (pinfunction "P2.1_19") (pintype "passive"))
    )
    (net (code "14") (name "/IN8") (class "Default")
      (node (ref "D15") (pin "K") (pinfunction "K_K") (pintype "passive"))
      (node (ref "U11") (pin "4") (pinfunction "C_4") (pintype "passive"))
      (node (ref "U2") (pin "20") (pinfunction "P2.2_20") (pintype "passive"))
    )
    (net (code "15") (name "/IN9") (class "Default")
      (node (ref "D16") (pin "K") (pinfunction "K_K") (pintype "passive"))
      (node (ref "U12") (pin "4") (pinfunction "C_4") (pintype "passive"))
      (node (ref "U2") (pin "21") (pinfunction "P2.3_21") (pintype "passive"))
    )
    (net (code "16") (name "/IN10") (class "Default")
      (node (ref "D17") (pin "K") (pinfunction "K_K") (pintype "passive"))
      (node (ref "U13") (pin "4") (pinfunction "C_4") (pintype "passive"))
      (node (ref "U2") (pin "22") (pinfunction "P2.4_22") (pintype "passive"))
    )
    (net (code "17") (name "/IN11") (class "Default")
      (node (ref "D18") (pin "K") (pinfunction "K_K") (pintype "passive"))
      (node (ref "U14") (pin "4") (pinfunction "C_4") (pintype "passive"))
      (node (ref "U2") (pin "23") (pinfunction "P2.5_23") (pintype "passive"))
    )
    (net (code "18") (name "/IN12") (class "Default")
      (node (ref "D19") (pin "K") (pinfunction "K_K") (pintype "passive"))
      (node (ref "U15") (pin "4") (pinfunction "C_4") (pintype "passive"))
      (node (ref "U2") (pin "24") (pinfunction "P2.6_24") (pintype "passive"))
    )
    (net (code "19") (name "/INPUT1") (class "Default")
      (node (ref "P3") (pin "2") (pinfunction "2_2") (pintype "passive"))
      (node (ref "U4") (pin "2") (pinfunction "K_2") (pintype "passive"))
    )
    (net (code "20") (name "/INPUT2") (class "Default")
      (node (ref "P4") (pin "2") (pinfunction "2_2") (pintype "passive"))
      (node (ref "U5") (pin "2") (pinfunction "K_2") (pintype "passive"))
    )
    (net (code "21") (name "/INPUT3") (class "Default")
      (node (ref "P5") (pin "2") (pinfunction "2_2") (pintype "passive"))
      (node (ref "U6") (pin "2") (pinfunction "K_2") (pintype "passive"))
    )
    (net (code "22") (name "/INPUT4") (class "Default")
      (node (ref "P6") (pin "2") (pinfunction "2_2") (pintype "passive"))
      (node (ref "U7") (pin "2") (pinfunction "K_2") (pintype "passive"))
    )
    (net (code "23") (name "/INPUT5") (class "Default")
      (node (ref "P7") (pin "2") (pinfunction "2_2") (pintype "passive"))
      (node (ref "U8") (pin "2") (pinfunction "K_2") (pintype "passive"))
    )
    (net (code "24") (name "/INPUT6") (class "Default")
      (node (ref "P8") (pin "2") (pinfunction "2_2") (pintype "passive"))
      (node (ref "U9") (pin "2") (pinfunction "K_2") (pintype "passive"))
    )
    (net (code "25") (name "/INPUT7") (class "Default")
      (node (ref "P9") (pin "2") (pinfunction "2_2") (pintype "passive"))
      (node (ref "U10") (pin "2") (pinfunction "K_2") (pintype "passive"))
    )
    (net (code "26") (name "/INPUT8") (class "Default")
      (node (ref "P10") (pin "2") (pinfunction "2_2") (pintype "passive"))
      (node (ref "U11") (pin "2") (pinfunction "K_2") (pintype "passive"))
    )
    (net (code "27") (name "/INPUT9") (class "Default")
      (node (ref "P11") (pin "2") (pinfunction "2_2") (pintype "passive"))
      (node (ref "U12") (pin "2") (pinfunction "K_2") (pintype "passive"))
    )
    (net (code "28") (name "/INPUT10") (class "Default")
      (node (ref "P12") (pin "2") (pinfunction "2_2") (pintype "passive"))
      (node (ref "U13") (pin "2") (pinfunction "K_2") (pintype "passive"))
    )
    (net (code "29") (name "/INPUT11") (class "Default")
      (node (ref "P13") (pin "2") (pinfunction "2_2") (pintype "passive"))
      (node (ref "U14") (pin "2") (pinfunction "K_2") (pintype "passive"))
    )
    (net (code "30") (name "/INPUT12") (class "Default")
      (node (ref "P14") (pin "2") (pinfunction "2_2") (pintype "passive"))
      (node (ref "U15") (pin "2") (pinfunction "K_2") (pintype "passive"))
    )
    (net (code "31") (name "/LED") (class "Default")
      (node (ref "R9") (pin "2") (pinfunction "2_2") (pintype "passive"))
      (node (ref "U2") (pin "25") (pinfunction "P2.7_25") (pintype "passive"))
    )
    (net (code "32") (name "/MCU_RX") (class "Default")
      (node (ref "D6") (pin "1") (pinfunction "A_1") (pintype "passive"))
      (node (ref "U2") (pin "5") (pinfunction "P3.0/RXD_5") (pintype "passive"))
    )
    (net (code "33") (name "/MCU_TX") (class "Default")
      (node (ref "R20") (pin "2") (pinfunction "2_2") (pintype "passive"))
      (node (ref "U2") (pin "7") (pinfunction "P3.1/TXD_7") (pintype "passive"))
    )
    (net (code "34") (name "/O1") (class "Default")
      (node (ref "U16") (pin "2") (pinfunction "1Y_2") (pintype "passive"))
      (node (ref "U17") (pin "6") (pinfunction "IN6_6") (pintype "input"))
    )
    (net (code "35") (name "/O2") (class "Default")
      (node (ref "U16") (pin "4") (pinfunction "2Y_4") (pintype "passive"))
      (node (ref "U17") (pin "5") (pinfunction "IN5_5") (pintype "input"))
    )
    (net (code "36") (name "/O3") (class "Default")
      (node (ref "U16") (pin "6") (pinfunction "3Y_6") (pintype "passive"))
      (node (ref "U17") (pin "4") (pinfunction "IN4_4") (pintype "input"))
    )
    (net (code "37") (name "/O4") (class "Default")
      (node (ref "U16") (pin "8") (pinfunction "4Y_8") (pintype "passive"))
      (node (ref "U17") (pin "3") (pinfunction "IN3_3") (pintype "input"))
    )
    (net (code "38") (name "/O5") (class "Default")
      (node (ref "U16") (pin "10") (pinfunction "5Y_10") (pintype "passive"))
      (node (ref "U17") (pin "2") (pinfunction "IN2_2") (pintype "input"))
    )
    (net (code "39") (name "/O6") (class "Default")
      (node (ref "U16") (pin "12") (pinfunction "6Y_12") (pintype "passive"))
      (node (ref "U17") (pin "1") (pinfunction "IN1_1") (pintype "input"))
    )
    (net (code "40") (name "/O7") (class "Default")
      (node (ref "U18") (pin "2") (pinfunction "1Y_2") (pintype "passive"))
      (node (ref "U19") (pin "6") (pinfunction "IN6_6") (pintype "input"))
    )
    (net (code "41") (name "/O8") (class "Default")
      (node (ref "U18") (pin "4") (pinfunction "2Y_4") (pintype "passive"))
      (node (ref "U19") (pin "5") (pinfunction "IN5_5") (pintype "input"))
    )
    (net (code "42") (name "/O9") (class "Default")
      (node (ref "U18") (pin "6") (pinfunction "3Y_6") (pintype "passive"))
      (node (ref "U19") (pin "4") (pinfunction "IN4_4") (pintype "input"))
    )
    (net (code "43") (name "/O10") (class "Default")
      (node (ref "U18") (pin "8") (pinfunction "4Y_8") (pintype "passive"))
      (node (ref "U19") (pin "3") (pinfunction "IN3_3") (pintype "input"))
    )
    (net (code "44") (name "/O11") (class "Default")
      (node (ref "U18") (pin "10") (pinfunction "5Y_10") (pintype "passive"))
      (node (ref "U19") (pin "2") (pinfunction "IN2_2") (pintype "input"))
    )
    (net (code "45") (name "/O12") (class "Default")
      (node (ref "U18") (pin "12") (pinfunction "6Y_12") (pintype "passive"))
      (node (ref "U19") (pin "1") (pinfunction "IN1_1") (pintype "input"))
    )
    (net (code "46") (name "/OUT1") (class "Default")
      (node (ref "U16") (pin "1") (pinfunction "1A_1") (pintype "passive"))
      (node (ref "U2") (pin "32") (pinfunction "P0.5_32") (pintype "passive"))
    )
    (net (code "47") (name "/OUT2") (class "Default")
      (node (ref "U16") (pin "3") (pinfunction "2A_3") (pintype "passive"))
      (node (ref "U2") (pin "33") (pinfunction "P0.4_33") (pintype "passive"))
    )
    (net (code "48") (name "/OUT3") (class "Default")
      (node (ref "U16") (pin "5") (pinfunction "3A_5") (pintype "passive"))
      (node (ref "U2") (pin "34") (pinfunction "P0.3_34") (pintype "passive"))
    )
    (net (code "49") (name "/OUT4") (class "Default")
      (node (ref "U16") (pin "9") (pinfunction "4A_9") (pintype "passive"))
      (node (ref "U2") (pin "35") (pinfunction "P0.2_35") (pintype "passive"))
    )
    (net (code "50") (name "/OUT5") (class "Default")
      (node (ref "U16") (pin "11") (pinfunction "5A_11") (pintype "passive"))
      (node (ref "U2") (pin "36") (pinfunction "P0.1_36") (pintype "passive"))
    )
    (net (code "51") (name "/OUT5V_1") (class "Default")
      (node (ref "R13") (pin "1") (pinfunction "1_1") (pintype "passive"))
      (node (ref "U2") (pin "28") (pinfunction "P4.1_28") (pintype "passive"))
    )
    (net (code "52") (name "/OUT5V_2") (class "Default")
      (node (ref "R14") (pin "1") (pinfunction "1_1") (pintype "passive"))
      (node (ref "U2") (pin "30") (pinfunction "P0.7_30") (pintype "passive"))
    )
    (net (code "53") (name "/OUT5V_3") (class "Default")
      (node (ref "R15") (pin "1") (pinfunction "1_1") (pintype "passive"))
      (node (ref "U2") (pin "31") (pinfunction "P0.6_31") (pintype "passive"))
    )
    (net (code "54") (name "/OUT6") (class "Default")
      (node (ref "U16") (pin "13") (pinfunction "6A_13") (pintype "passive"))
      (node (ref "U2") (pin "37") (pinfunction "P0.0_37") (pintype "passive"))
    )
    (net (code "55") (name "/OUT7") (class "Default")
      (node (ref "U18") (pin "1") (pinfunction "1A_1") (pintype "passive"))
      (node (ref "U2") (pin "43") (pinfunction "P1.3_43") (pintype "passive"))
    )
    (net (code "56") (name "/OUT8") (class "Default")
      (node (ref "U18") (pin "3") (pinfunction "2A_3") (pintype "passive"))
      (node (ref "U2") (pin "44") (pinfunction "P1.4_44") (pintype "passive"))
    )
    (net (code "57") (name "/OUT9") (class "Default")
      (node (ref "U18") (pin "5") (pinfunction "3A_5") (pintype "passive"))
      (node (ref "U2") (pin "1") (pinfunction "P1.5_1") (pintype "passive"))
    )
    (net (code "58") (name "/OUT10") (class "Default")
      (node (ref "U18") (pin "9") (pinfunction "4A_9") (pintype "passive"))
      (node (ref "U2") (pin "40") (pinfunction "P1.0_40") (pintype "passive"))
    )
    (net (code "59") (name "/OUT11") (class "Default")
      (node (ref "U18") (pin "11") (pinfunction "5A_11") (pintype "passive"))
      (node (ref "U2") (pin "41") (pinfunction "P1.1_41") (pintype "passive"))
    )
    (net (code "60") (name "/OUT12") (class "Default")
      (node (ref "U18") (pin "13") (pinfunction "6A_13") (pintype "passive"))
      (node (ref "U2") (pin "42") (pinfunction "P1.2_42") (pintype "passive"))
    )
    (net (code "61") (name "/OUTPUT1") (class "Default")
      (node (ref "P15") (pin "1") (pinfunction "1_1") (pintype "passive"))
      (node (ref "R35") (pin "1") (pinfunction "1_1") (pintype "passive"))
      (node (ref "U17") (pin "11") (pinfunction "OUT6_11") (pintype "open_collector"))
    )
    (net (code "62") (name "/OUTPUT2") (class "Default")
      (node (ref "P16") (pin "1") (pinfunction "1_1") (pintype "passive"))
      (node (ref "R36") (pin "1") (pinfunction "1_1") (pintype "passive"))
      (node (ref "U17") (pin "12") (pinfunction "OUT5_12") (pintype "open_collector"))
    )
    (net (code "63") (name "/OUTPUT3") (class "Default")
      (node (ref "P17") (pin "1") (pinfunction "1_1") (pintype "passive"))
      (node (ref "R37") (pin "1") (pinfunction "1_1") (pintype "passive"))
      (node (ref "U17") (pin "13") (pinfunction "OUT4_13") (pintype "open_collector"))
    )
    (net (code "64") (name "/OUTPUT4") (class "Default")
      (node (ref "P18") (pin "1") (pinfunction "1_1") (pintype "passive"))
      (node (ref "R38") (pin "1") (pinfunction "1_1") (pintype "passive"))
      (node (ref "U17") (pin "14") (pinfunction "OUT3_14") (pintype "open_collector"))
    )
    (net (code "65") (name "/OUTPUT5") (class "Default")
      (node (ref "P19") (pin "1") (pinfunction "1_1") (pintype "passive"))
      (node (ref "R39") (pin "1") (pinfunction "1_1") (pintype "passive"))
      (node (ref "U17") (pin "15") (pinfunction "OUT2_15") (pintype "open_collector"))
    )
    (net (code "66") (name "/OUTPUT6") (class "Default")
      (node (ref "P20") (pin "1") (pinfunction "1_1") (pintype "passive"))
      (node (ref "R40") (pin "1") (pinfunction "1_1") (pintype "passive"))
      (node (ref "U17") (pin "16") (pinfunction "OUT1_16") (pintype "open_collector"))
    )
    (net (code "67") (name "/OUTPUT7") (class "Default")
      (node (ref "P21") (pin "1") (pinfunction "1_1") (pintype "passive"))
      (node (ref "R41") (pin "1") (pinfunction "1_1") (pintype "passive"))
      (node (ref "U19") (pin "11") (pinfunction "OUT6_11") (pintype "open_collector"))
    )
    (net (code "68") (name "/OUTPUT8") (class "Default")
      (node (ref "P22") (pin "1") (pinfunction "1_1") (pintype "passive"))
      (node (ref "R42") (pin "1") (pinfunction "1_1") (pintype "passive"))
      (node (ref "U19") (pin "12") (pinfunction "OUT5_12") (pintype "open_collector"))
    )
    (net (code "69") (name "/OUTPUT9") (class "Default")
      (node (ref "P23") (pin "1") (pinfunction "1_1") (pintype "passive"))
      (node (ref "R43") (pin "1") (pinfunction "1_1") (pintype "passive"))
      (node (ref "U19") (pin "13") (pinfunction "OUT4_13") (pintype "open_collector"))
    )
    (net (code "70") (name "/OUTPUT10") (class "Default")
      (node (ref "P24") (pin "1") (pinfunction "1_1") (pintype "passive"))
      (node (ref "R44") (pin "1") (pinfunction "1_1") (pintype "passive"))
      (node (ref "U19") (pin "14") (pinfunction "OUT3_14") (pintype "open_collector"))
    )
    (net (code "71") (name "/OUTPUT11") (class "Default")
      (node (ref "P25") (pin "1") (pinfunction "1_1") (pintype "passive"))
      (node (ref "R45") (pin "1") (pinfunction "1_1") (pintype "passive"))
      (node (ref "U19") (pin "15") (pinfunction "OUT2_15") (pintype "open_collector"))
    )
    (net (code "72") (name "/OUTPUT12") (class "Default")
      (node (ref "P26") (pin "1") (pinfunction "1_1") (pintype "passive"))
      (node (ref "R46") (pin "1") (pinfunction "1_1") (pintype "passive"))
      (node (ref "U19") (pin "16") (pinfunction "OUT1_16") (pintype "open_collector"))
    )
    (net (code "73") (name "/SCL") (class "Default")
      (node (ref "R16") (pin "1") (pinfunction "1_1") (pintype "passive"))
      (node (ref "U2") (pin "3") (pinfunction "P1.7_3") (pintype "passive"))
      (node (ref "U3") (pin "6") (pinfunction "SCL_6") (pintype "passive"))
    )
    (net (code "74") (name "/SDA") (class "Default")
      (node (ref "R17") (pin "1") (pinfunction "1_1") (pintype "passive"))
      (node (ref "U2") (pin "2") (pinfunction "P1.6_2") (pintype "passive"))
      (node (ref "U3") (pin "5") (pinfunction "SDA_5") (pintype "passive"))
    )
    (net (code "75") (name "/USB_D+") (class "Default")
      (node (ref "IC1") (pin "15") (pinfunction "USBDP_15") (pintype "passive"))
      (node (ref "USB1") (pin "3") (pinfunction "USB+_3") (pintype "passive"))
    )
    (net (code "76") (name "/USB_D-") (class "Default")
      (node (ref "IC1") (pin "16") (pinfunction "USBDM_16") (pintype "passive"))
      (node (ref "USB1") (pin "2") (pinfunction "USB-_2") (pintype "passive"))
    )
    (net (code "77") (name "/USB_VBUS") (class "Default")
      (node (ref "L2") (pin "2") (pinfunction "2_2") (pintype "passive"))
      (node (ref "USB1") (pin "1") (pinfunction "VCC_1") (pintype "passive"))
    )
    (net (code "78") (name "/VCCIO") (class "Default")
      (node (ref "C13") (pin "2") (pinfunction "2_2") (pintype "passive"))
      (node (ref "IC1") (pin "17") (pinfunction "3V3OUT_17") (pintype "passive"))
      (node (ref "IC1") (pin "4") (pinfunction "VCCIO_4") (pintype "passive"))
    )
    (net (code "79") (name "GND") (class "Default")
      (node (ref "C10") (pin "2") (pinfunction "2_2") (pintype "passive"))
      (node (ref "C11") (pin "1") (pinfunction "1_1") (pintype "passive"))
      (node (ref "C12") (pin "1") (pinfunction "1_1") (pintype "passive"))
      (node (ref "C13") (pin "1") (pinfunction "1_1") (pintype "passive"))
      (node (ref "C14") (pin "1") (pinfunction "1_1") (pintype "passive"))
      (node (ref "C15") (pin "2") (pinfunction "2_2") (pintype "passive"))
      (node (ref "C16") (pin "1") (pinfunction "1_1") (pintype "passive"))
      (node (ref "C17") (pin "1") (pinfunction "1_1") (pintype "passive"))
      (node (ref "C18") (pin "1") (pinfunction "1_1") (pintype "passive"))
      (node (ref "C19") (pin "1") (pinfunction "1_1") (pintype "passive"))
      (node (ref "C2") (pin "1") (pinfunction "1_1") (pintype "passive"))
      (node (ref "C3") (pin "1") (pinfunction "1_1") (pintype "passive"))
      (node (ref "C6") (pin "2") (pinfunction "2_2") (pintype "passive"))
      (node (ref "C7") (pin "2") (pinfunction "2_2") (pintype "passive"))
      (node (ref "C8") (pin "2") (pinfunction "2_2") (pintype "passive"))
      (node (ref "C9") (pin "2") (pinfunction "2_2") (pintype "passive"))
      (node (ref "D1") (pin "1") (pinfunction "A_1") (pintype "passive"))
      (node (ref "D3") (pin "K") (pinfunction "K_K") (pintype "passive"))
      (node (ref "D4") (pin "K") (pinfunction "K_K") (pintype "passive"))
      (node (ref "IC1") (pin "18") (pinfunction "GND_18") (pintype "passive"))
      (node (ref "IC1") (pin "21") (pinfunction "GND_21") (pintype "passive"))
      (node (ref "IC1") (pin "25") (pinfunction "AGND_25") (pintype "passive"))
      (node (ref "IC1") (pin "26") (pinfunction "TEST_26") (pintype "passive"))
      (node (ref "IC1") (pin "7") (pinfunction "GND_7") (pintype "passive"))
      (node (ref "P1") (pin "2") (pinfunction "2_2") (pintype "passive"))
      (node (ref "P10") (pin "3") (pinfunction "3_3") (pintype "passive"))
      (node (ref "P11") (pin "3") (pinfunction "3_3") (pintype "passive"))
      (node (ref "P12") (pin "3") (pinfunction "3_3") (pintype "passive"))
      (node (ref "P13") (pin "3") (pinfunction "3_3") (pintype "passive"))
      (node (ref "P14") (pin "3") (pinfunction "3_3") (pintype "passive"))
      (node (ref "P3") (pin "3") (pinfunction "3_3") (pintype "passive"))
      (node (ref "P4") (pin "3") (pinfunction "3_3") (pintype "passive"))
      (node (ref "P5") (pin "3") (pinfunction "3_3") (pintype "passive"))
      (node (ref "P6") (pin "3") (pinfunction "3_3") (pintype "passive"))
      (node (ref "P7") (pin "3") (pinfunction "3_3") (pintype "passive"))
      (node (ref "P8") (pin "3") (pinfunction "3_3") (pintype "passive"))
      (node (ref "P9") (pin "3") (pinfunction "3_3") (pintype "passive"))
      (node (ref "R10") (pin "1") (pinfunction "1_1") (pintype "passive"))
      (node (ref "R11") (pin "1") (pinfunction "1_1") (pintype "passive"))
      (node (ref "R12") (pin "1") (pinfunction "1_1") (pintype "passive"))
      (node (ref "R2") (pin "1") (pinfunction "1_1") (pintype "passive"))
      (node (ref "R22") (pin "1") (pinfunction "1_1") (pintype "passive"))
      (node (ref "R4") (pin "2") (pinfunction "2_2") (pintype "passive"))
      (node (ref "R8") (pin "2") (pinfunction "2_2") (pintype "passive"))
      (node (ref "U1") (pin "2") (pinfunction "GND_2") (pintype "passive"))
      (node (ref "U10") (pin "3") (pinfunction "E_3") (pintype "passive"))
      (node (ref "U11") (pin "3") (pinfunction "E_3") (pintype "passive"))
      (node (ref "U12") (pin "3") (pinfunction "E_3") (pintype "passive"))
      (node (ref "U13") (pin "3") (pinfunction "E_3") (pintype "passive"))
      (node (ref "U14") (pin "3") (pinfunction "E_3") (pintype "passive"))
      (node (ref "U15") (pin "3") (pinfunction "E_3") (pintype "passive"))
      (node (ref "U16") (pin "7") (pinfunction "GND_7") (pintype "passive"))
      (node (ref "U17") (pin "8") (pinfunction "GND_8") (pintype "power_in"))
      (node (ref "U18") (pin "7") (pinfunction "GND_7") (pintype "passive"))
      (node (ref "U19") (pin "8") (pinfunction "GND_8") (pintype "power_in"))
      (node (ref "U2") (pin "16") (pinfunction "GND_16") (pintype "power_in"))
      (node (ref "U3") (pin "1") (pinfunction "A0_1") (pintype "passive"))
      (node (ref "U3") (pin "2") (pinfunction "A1_2") (pintype "passive"))
      (node (ref "U3") (pin "3") (pinfunction "A3_3") (pintype "passive"))
      (node (ref "U3") (pin "4") (pinfunction "GND_4") (pintype "passive"))
      (node (ref "U3") (pin "7") (pinfunction "WP_7") (pintype "passive"))
      (node (ref "U4") (pin "3") (pinfunction "E_3") (pintype "passive"))
      (node (ref "U5") (pin "3") (pinfunction "E_3") (pintype "passive"))
      (node (ref "U6") (pin "3") (pinfunction "E_3") (pintype "passive"))
      (node (ref "U7") (pin "3") (pinfunction "E_3") (pintype "passive"))
      (node (ref "U8") (pin "3") (pinfunction "E_3") (pintype "passive"))
      (node (ref "U9") (pin "3") (pinfunction "E_3") (pintype "passive"))
      (node (ref "USB1") (pin "4") (pinfunction "GND_4") (pintype "passive"))
    )
    (net (code "80") (name "Net-(C15-Pad1)") (class "Default")
      (node (ref "C15") (pin "1") (pinfunction "1_1") (pintype "passive"))
      (node (ref "R22") (pin "2") (pinfunction "2_2") (pintype "passive"))
      (node (ref "USB1") (pin "5") (pinfunction "NC_5") (pintype "passive"))
      (node (ref "USB1") (pin "6") (pinfunction "NC_6") (pintype "passive"))
    )
    (net (code "81") (name "Net-(D1-K)") (class "Default")
      (node (ref "C1") (pin "1") (pinfunction "1_1") (pintype "passive"))
      (node (ref "D1") (pin "2") (pinfunction "K_2") (pintype "passive"))
      (node (ref "L1") (pin "1") (pinfunction "1_1") (pintype "passive"))
      (node (ref "U1") (pin "6") (pinfunction "SW_6") (pintype "passive"))
    )
    (net (code "82") (name "Net-(D3-PadA)") (class "Default")
      (node (ref "D3") (pin "A") (pinfunction "A_A") (pintype "passive"))
      (node (ref "R1") (pin "2") (pinfunction "2_2") (pintype "passive"))
    )
    (net (code "83") (name "Net-(D4-PadA)") (class "Default")
      (node (ref "D4") (pin "A") (pinfunction "A_A") (pintype "passive"))
      (node (ref "R9") (pin "1") (pinfunction "1_1") (pintype "passive"))
    )
    (net (code "84") (name "Net-(D5-PadK)") (class "Default")
      (node (ref "D5") (pin "K") (pinfunction "K_K") (pintype "passive"))
      (node (ref "R18") (pin "2") (pinfunction "2_2") (pintype "passive"))
    )
    (net (code "85") (name "Net-(D6-K)") (class "Default")
      (node (ref "D6") (pin "2") (pinfunction "K_2") (pintype "passive"))
      (node (ref "IC1") (pin "1") (pinfunction "TXD_1") (pintype "passive"))
    )
    (net (code "86") (name "Net-(D7-PadK)") (class "Default")
      (node (ref "D7") (pin "K") (pinfunction "K_K") (pintype "passive"))
      (node (ref "R19") (pin "2") (pinfunction "2_2") (pintype "passive"))
    )
    (net (code "87") (name "Net-(D8-PadA)") (class "Default")
      (node (ref "D8") (pin "A") (pinfunction "A_A") (pintype "passive"))
      (node (ref "R47") (pin "1") (pinfunction "1_1") (pintype "passive"))
    )
    (net (code "88") (name "Net-(D9-PadA)") (class "Default")
      (node (ref "D9") (pin "A") (pinfunction "A_A") (pintype "passive"))
      (node (ref "R48") (pin "1") (pinfunction "1_1") (pintype "passive"))
    )
    (net (code "89") (name "Net-(D10-PadA)") (class "Default")
      (node (ref "D10") (pin "A") (pinfunction "A_A") (pintype "passive"))
      (node (ref "R49") (pin "1") (pinfunction "1_1") (pintype "passive"))
    )
    (net (code "90") (name "Net-(D11-PadA)") (class "Default")
      (node (ref "D11") (pin "A") (pinfunction "A_A") (pintype "passive"))
      (node (ref "R50") (pin "1") (pinfunction "1_1") (pintype "passive"))
    )
    (net (code "91") (name "Net-(D12-PadA)") (class "Default")
      (node (ref "D12") (pin "A") (pinfunction "A_A") (pintype "passive"))
      (node (ref "R51") (pin "1") (pinfunction "1_1") (pintype "passive"))
    )
    (net (code "92") (name "Net-(D13-PadA)") (class "Default")
      (node (ref "D13") (pin "A") (pinfunction "A_A") (pintype "passive"))
      (node (ref "R52") (pin "1") (pinfunction "1_1") (pintype "passive"))
    )
    (net (code "93") (name "Net-(D14-PadA)") (class "Default")
      (node (ref "D14") (pin "A") (pinfunction "A_A") (pintype "passive"))
      (node (ref "R53") (pin "1") (pinfunction "1_1") (pintype "passive"))
    )
    (net (code "94") (name "Net-(D15-PadA)") (class "Default")
      (node (ref "D15") (pin "A") (pinfunction "A_A") (pintype "passive"))
      (node (ref "R54") (pin "1") (pinfunction "1_1") (pintype "passive"))
    )
    (net (code "95") (name "Net-(D16-PadA)") (class "Default")
      (node (ref "D16") (pin "A") (pinfunction "A_A") (pintype "passive"))
      (node (ref "R55") (pin "1") (pinfunction "1_1") (pintype "passive"))
    )
    (net (code "96") (name "Net-(D17-PadA)") (class "Default")
      (node (ref "D17") (pin "A") (pinfunction "A_A") (pintype "passive"))
      (node (ref "R56") (pin "1") (pinfunction "1_1") (pintype "passive"))
    )
    (net (code "97") (name "Net-(D18-PadA)") (class "Default")
      (node (ref "D18") (pin "A") (pinfunction "A_A") (pintype "passive"))
      (node (ref "R57") (pin "1") (pinfunction "1_1") (pintype "passive"))
    )
    (net (code "98") (name "Net-(D19-PadA)") (class "Default")
      (node (ref "D19") (pin "A") (pinfunction "A_A") (pintype "passive"))
      (node (ref "R58") (pin "1") (pinfunction "1_1") (pintype "passive"))
    )
    (net (code "99") (name "Net-(D20-PadK)") (class "Default")
      (node (ref "D20") (pin "K") (pinfunction "K_K") (pintype "passive"))
      (node (ref "R35") (pin "2") (pinfunction "2_2") (pintype "passive"))
    )
    (net (code "100") (name "Net-(D21-PadK)") (class "Default")
      (node (ref "D21") (pin "K") (pinfunction "K_K") (pintype "passive"))
      (node (ref "R36") (pin "2") (pinfunction "2_2") (pintype "passive"))
    )
    (net (code "101") (name "Net-(D22-PadK)") (class "Default")
      (node (ref "D22") (pin "K") (pinfunction "K_K") (pintype "passive"))
      (node (ref "R37") (pin "2") (pinfunction "2_2") (pintype "passive"))
    )
    (net (code "102") (name "Net-(D23-PadK)") (class "Default")
      (node (ref "D23") (pin "K") (pinfunction "K_K") (pintype "passive"))
      (node (ref "R38") (pin "2") (pinfunction "2_2") (pintype "passive"))
    )
    (net (code "103") (name "Net-(D24-PadK)") (class "Default")
      (node (ref "D24") (pin "K") (pinfunction "K_K") (pintype "passive"))
      (node (ref "R39") (pin "2") (pinfunction "2_2") (pintype "passive"))
    )
    (net (code "104") (name "Net-(D25-PadK)") (class "Default")
      (node (ref "D25") (pin "K") (pinfunction "K_K") (pintype "passive"))
      (node (ref "R40") (pin "2") (pinfunction "2_2") (pintype "passive"))
    )
    (net (code "105") (name "Net-(D26-PadK)") (class "Default")
      (node (ref "D26") (pin "K") (pinfunction "K_K") (pintype "passive"))
      (node (ref "R41") (pin "2") (pinfunction "2_2") (pintype "passive"))
    )
    (net (code "106") (name "Net-(D27-PadK)") (class "Default")
      (node (ref "D27") (pin "K") (pinfunction "K_K") (pintype "passive"))
      (node (ref "R42") (pin "2") (pinfunction "2_2") (pintype "passive"))
    )
    (net (code "107") (name "Net-(D28-PadK)") (class "Default")
      (node (ref "D28") (pin "K") (pinfunction "K_K") (pintype "passive"))
      (node (ref "R43") (pin "2") (pinfunction "2_2") (pintype "passive"))
    )
    (net (code "108") (name "Net-(D29-PadK)") (class "Default")
      (node (ref "D29") (pin "K") (pinfunction "K_K") (pintype "passive"))
      (node (ref "R44") (pin "2") (pinfunction "2_2") (pintype "passive"))
    )
    (net (code "109") (name "Net-(D30-PadK)") (class "Default")
      (node (ref "D30") (pin "K") (pinfunction "K_K") (pintype "passive"))
      (node (ref "R45") (pin "2") (pinfunction "2_2") (pintype "passive"))
    )
    (net (code "110") (name "Net-(D31-PadK)") (class "Default")
      (node (ref "D31") (pin "K") (pinfunction "K_K") (pintype "passive"))
      (node (ref "R46") (pin "2") (pinfunction "2_2") (pintype "passive"))
    )
    (net (code "111") (name "Net-(IC1-CBUS0)") (class "Default")
      (node (ref "IC1") (pin "23") (pinfunction "CBUS0_23") (pintype "passive"))
      (node (ref "R18") (pin "1") (pinfunction "1_1") (pintype "passive"))
    )
    (net (code "112") (name "Net-(IC1-CBUS1)") (class "Default")
      (node (ref "IC1") (pin "22") (pinfunction "CBUS1_22") (pintype "passive"))
      (node (ref "R19") (pin "1") (pinfunction "1_1") (pintype "passive"))
    )
    (net (code "113") (name "Net-(IC1-RESET#)") (class "Default")
      (node (ref "C14") (pin "2") (pinfunction "2_2") (pintype "passive"))
      (node (ref "IC1") (pin "19") (pinfunction "RESET#_19") (pintype "passive"))
      (node (ref "R21") (pin "2") (pinfunction "2_2") (pintype "passive"))
    )
    (net (code "114") (name "Net-(IC1-RXD)") (class "Default")
      (node (ref "IC1") (pin "5") (pinfunction "RXD_5") (pintype "passive"))
      (node (ref "R20") (pin "1") (pinfunction "1_1") (pintype "passive"))
    )
    (net (code "115") (name "Net-(IC1-VCC)") (class "Default")
      (node (ref "C11") (pin "2") (pinfunction "2_2") (pintype "passive"))
      (node (ref "C12") (pin "2") (pinfunction "2_2") (pintype "passive"))
      (node (ref "D5") (pin "A") (pinfunction "A_A") (pintype "passive"))
      (node (ref "D7") (pin "A") (pinfunction "A_A") (pintype "passive"))
      (node (ref "IC1") (pin "20") (pinfunction "VCC_20") (pintype "passive"))
      (node (ref "L2") (pin "1") (pinfunction "1_1") (pintype "passive"))
      (node (ref "R21") (pin "1") (pinfunction "1_1") (pintype "passive"))
    )
    (net (code "116") (name "Net-(Q1-B)") (class "Default")
      (node (ref "Q1") (pin "1") (pinfunction "B_1") (pintype "passive"))
      (node (ref "R13") (pin "2") (pinfunction "2_2") (pintype "passive"))
    )
    (net (code "117") (name "Net-(Q2-B)") (class "Default")
      (node (ref "Q2") (pin "1") (pinfunction "B_1") (pintype "passive"))
      (node (ref "R14") (pin "2") (pinfunction "2_2") (pintype "passive"))
    )
    (net (code "118") (name "Net-(Q3-B)") (class "Default")
      (node (ref "Q3") (pin "1") (pinfunction "B_1") (pintype "passive"))
      (node (ref "R15") (pin "2") (pinfunction "2_2") (pintype "passive"))
    )
    (net (code "119") (name "Net-(U1-BST)") (class "Default")
      (node (ref "C1") (pin "2") (pinfunction "2_2") (pintype "passive"))
      (node (ref "U1") (pin "1") (pinfunction "BST_1") (pintype "passive"))
    )
    (net (code "120") (name "Net-(U1-EN)") (class "Default")
      (node (ref "R3") (pin "2") (pinfunction "2_2") (pintype "passive"))
      (node (ref "R4") (pin "1") (pinfunction "1_1") (pintype "passive"))
      (node (ref "U1") (pin "4") (pinfunction "EN_4") (pintype "passive"))
    )
    (net (code "121") (name "Net-(U1-FB)") (class "Default")
      (node (ref "C4") (pin "1") (pinfunction "1_1") (pintype "passive"))
      (node (ref "R2") (pin "2") (pinfunction "2_2") (pintype "passive"))
      (node (ref "R5") (pin "1") (pinfunction "1_1") (pintype "passive"))
      (node (ref "U1") (pin "3") (pinfunction "FB_3") (pintype "passive"))
    )
    (net (code "122") (name "Net-(U2-RST)") (class "Default")
      (node (ref "C5") (pin "1") (pinfunction "1_1") (pintype "passive"))
      (node (ref "R8") (pin "1") (pinfunction "1_1") (pintype "passive"))
      (node (ref "S1") (pin "2") (pinfunction "2_2") (pintype "passive"))
      (node (ref "U2") (pin "4") (pinfunction "RST_4") (pintype "passive"))
    )
    (net (code "123") (name "Net-(U2-XTAL1)") (class "Default")
      (node (ref "C7") (pin "1") (pinfunction "1_1") (pintype "passive"))
      (node (ref "U2") (pin "15") (pinfunction "XTAL1_15") (pintype "passive"))
      (node (ref "Y1") (pin "1") (pinfunction "OSC1_1") (pintype "passive"))
    )
    (net (code "124") (name "Net-(U2-XTAL2)") (class "Default")
      (node (ref "C6") (pin "1") (pinfunction "1_1") (pintype "passive"))
      (node (ref "U2") (pin "14") (pinfunction "XTAL2_14") (pintype "passive"))
      (node (ref "Y1") (pin "2") (pinfunction "OSC2_2") (pintype "passive"))
    )
    (net (code "125") (name "Net-(U4-A)") (class "Default")
      (node (ref "R23") (pin "2") (pinfunction "2_2") (pintype "passive"))
      (node (ref "U4") (pin "1") (pinfunction "A_1") (pintype "passive"))
    )
    (net (code "126") (name "Net-(U5-A)") (class "Default")
      (node (ref "R24") (pin "2") (pinfunction "2_2") (pintype "passive"))
      (node (ref "U5") (pin "1") (pinfunction "A_1") (pintype "passive"))
    )
    (net (code "127") (name "Net-(U6-A)") (class "Default")
      (node (ref "R25") (pin "2") (pinfunction "2_2") (pintype "passive"))
      (node (ref "U6") (pin "1") (pinfunction "A_1") (pintype "passive"))
    )
    (net (code "128") (name "Net-(U7-A)") (class "Default")
      (node (ref "R26") (pin "2") (pinfunction "2_2") (pintype "passive"))
      (node (ref "U7") (pin "1") (pinfunction "A_1") (pintype "passive"))
    )
    (net (code "129") (name "Net-(U8-A)") (class "Default")
      (node (ref "R27") (pin "2") (pinfunction "2_2") (pintype "passive"))
      (node (ref "U8") (pin "1") (pinfunction "A_1") (pintype "passive"))
    )
    (net (code "130") (name "Net-(U9-A)") (class "Default")
      (node (ref "R28") (pin "2") (pinfunction "2_2") (pintype "passive"))
      (node (ref "U9") (pin "1") (pinfunction "A_1") (pintype "passive"))
    )
    (net (code "131") (name "Net-(U10-A)") (class "Default")
      (node (ref "R29") (pin "2") (pinfunction "2_2") (pintype "passive"))
      (node (ref "U10") (pin "1") (pinfunction "A_1") (pintype "passive"))
    )
    (net (code "132") (name "Net-(U11-A)") (class "Default")
      (node (ref "R30") (pin "2") (pinfunction "2_2") (pintype "passive"))
      (node (ref "U11") (pin "1") (pinfunction "A_1") (pintype "passive"))
    )
    (net (code "133") (name "Net-(U12-A)") (class "Default")
      (node (ref "R31") (pin "2") (pinfunction "2_2") (pintype "passive"))
      (node (ref "U12") (pin "1") (pinfunction "A_1") (pintype "passive"))
    )
    (net (code "134") (name "Net-(U13-A)") (class "Default")
      (node (ref "R32") (pin "2") (pinfunction "2_2") (pintype "passive"))
      (node (ref "U13") (pin "1") (pinfunction "A_1") (pintype "passive"))
    )
    (net (code "135") (name "Net-(U14-A)") (class "Default")
      (node (ref "R33") (pin "2") (pinfunction "2_2") (pintype "passive"))
      (node (ref "U14") (pin "1") (pinfunction "A_1") (pintype "passive"))
    )
    (net (code "136") (name "Net-(U15-A)") (class "Default")
      (node (ref "R34") (pin "2") (pinfunction "2_2") (pintype "passive"))
      (node (ref "U15") (pin "1") (pinfunction "A_1") (pintype "passive"))
    )
    (net (code "137") (name "V_COM") (class "Default")
      (node (ref "P3") (pin "1") (pinfunction "1_1") (pintype "passive"))
      (node (ref "P4") (pin "1") (pinfunction "1_1") (pintype "passive"))
      (node (ref "P5") (pin "1") (pinfunction "1_1") (pintype "passive"))
      (node (ref "P6") (pin "1") (pinfunction "1_1") (pintype "passive"))
      (node (ref "R23") (pin "1") (pinfunction "1_1") (pintype "passive"))
      (node (ref "R24") (pin "1") (pinfunction "1_1") (pintype "passive"))
      (node (ref "R25") (pin "1") (pinfunction "1_1") (pintype "passive"))
      (node (ref "R26") (pin "1") (pinfunction "1_1") (pintype "passive"))
      (node (ref "R6") (pin "1") (pinfunction "1_1") (pintype "passive"))
      (node (ref "R7") (pin "1") (pinfunction "1_1") (pintype "passive"))
    )
    (net (code "138") (name "Vin") (class "Default")
      (node (ref "D2") (pin "1") (pinfunction "A_1") (pintype "passive"))
      (node (ref "P1") (pin "1") (pinfunction "1_1") (pintype "passive"))
    )
    (net (code "139") (name "unconnected-(IC1-CBUS2-Pad14)") (class "Default")
      (node (ref "IC1") (pin "14") (pinfunction "CBUS2_14") (pintype "passive"))
    )
    (net (code "140") (name "unconnected-(IC1-CBUS3-Pad13)") (class "Default")
      (node (ref "IC1") (pin "13") (pinfunction "CBUS3_13") (pintype "passive"))
    )
    (net (code "141") (name "unconnected-(IC1-CBUS4-Pad12)") (class "Default")
      (node (ref "IC1") (pin "12") (pinfunction "CBUS4_12") (pintype "passive"))
    )
    (net (code "142") (name "unconnected-(IC1-CTS#-Pad11)") (class "Default")
      (node (ref "IC1") (pin "11") (pinfunction "CTS#_11") (pintype "passive"))
    )
    (net (code "143") (name "unconnected-(IC1-DCD#-Pad10)") (class "Default")
      (node (ref "IC1") (pin "10") (pinfunction "DCD#_10") (pintype "passive"))
    )
    (net (code "144") (name "unconnected-(IC1-DSR#-Pad9)") (class "Default")
      (node (ref "IC1") (pin "9") (pinfunction "DSR#_9") (pintype "passive"))
    )
    (net (code "145") (name "unconnected-(IC1-DTR#-Pad2)") (class "Default")
      (node (ref "IC1") (pin "2") (pinfunction "DTR#_2") (pintype "passive"))
    )
    (net (code "146") (name "unconnected-(IC1-NC-Pad8)") (class "Default")
      (node (ref "IC1") (pin "8") (pinfunction "NC_8") (pintype "passive"))
    )
    (net (code "147") (name "unconnected-(IC1-NC-Pad24)") (class "Default")
      (node (ref "IC1") (pin "24") (pinfunction "NC_24") (pintype "passive"))
    )
    (net (code "148") (name "unconnected-(IC1-OSCI-Pad27)") (class "Default")
      (node (ref "IC1") (pin "27") (pinfunction "OSCI_27") (pintype "passive"))
    )
    (net (code "149") (name "unconnected-(IC1-OSCO-Pad28)") (class "Default")
      (node (ref "IC1") (pin "28") (pinfunction "OSCO_28") (pintype "passive"))
    )
    (net (code "150") (name "unconnected-(IC1-RI#-Pad6)") (class "Default")
      (node (ref "IC1") (pin "6") (pinfunction "RI#_6") (pintype "passive"))
    )
    (net (code "151") (name "unconnected-(IC1-RTS#-Pad3)") (class "Default")
      (node (ref "IC1") (pin "3") (pinfunction "RTS#_3") (pintype "passive"))
    )
    (net (code "152") (name "unconnected-(U2-ALE-Pad27)") (class "Default")
      (node (ref "U2") (pin "27") (pinfunction "ALE_27") (pintype "passive"))
    )
    (net (code "153") (name "unconnected-(U2-EX_LVD-Pad29)") (class "Default")
      (node (ref "U2") (pin "29") (pinfunction "EX_LVD_29") (pintype "passive"))
    )
    (net (code "154") (name "unconnected-(U2-NA-Pad26)") (class "Default")
      (node (ref "U2") (pin "26") (pinfunction "NA_26") (pintype "passive"))
    )
    (net (code "155") (name "unconnected-(U2-P3.2-Pad8)") (class "Default")
      (node (ref "U2") (pin "8") (pinfunction "P3.2_8") (pintype "passive"))
    )
    (net (code "156") (name "unconnected-(U2-P4.0-Pad17)") (class "Default")
      (node (ref "U2") (pin "17") (pinfunction "P4.0_17") (pintype "passive"))
    )
    (net (code "157") (name "unconnected-(U2-P4.2-Pad39)") (class "Default")
      (node (ref "U2") (pin "39") (pinfunction "P4.2_39") (pintype "passive"))
    )
    (net (code "158") (name "unconnected-(U2-P4.3-Pad6)") (class "Default")
      (node (ref "U2") (pin "6") (pinfunction "P4.3_6") (pintype "passive"))
    )
    (net (code "159") (name "unconnected-(U17-IN7-Pad7)") (class "Default")
      (node (ref "U17") (pin "7") (pinfunction "IN7_7") (pintype "input"))
    )
    (net (code "160") (name "unconnected-(U17-OUT7-Pad10)") (class "Default")
      (node (ref "U17") (pin "10") (pinfunction "OUT7_10") (pintype "open_collector"))
    )
    (net (code "161") (name "unconnected-(U19-IN7-Pad7)") (class "Default")
      (node (ref "U19") (pin "7") (pinfunction "IN7_7") (pintype "input"))
    )
    (net (code "162") (name "unconnected-(U19-OUT7-Pad10)") (class "Default")
      (node (ref "U19") (pin "10") (pinfunction "OUT7_10") (pintype "open_collector"))
    )
  )
)
